# PCB_3U_SMA.net
KiCad netlist of a schematic drawn in Altium Designer
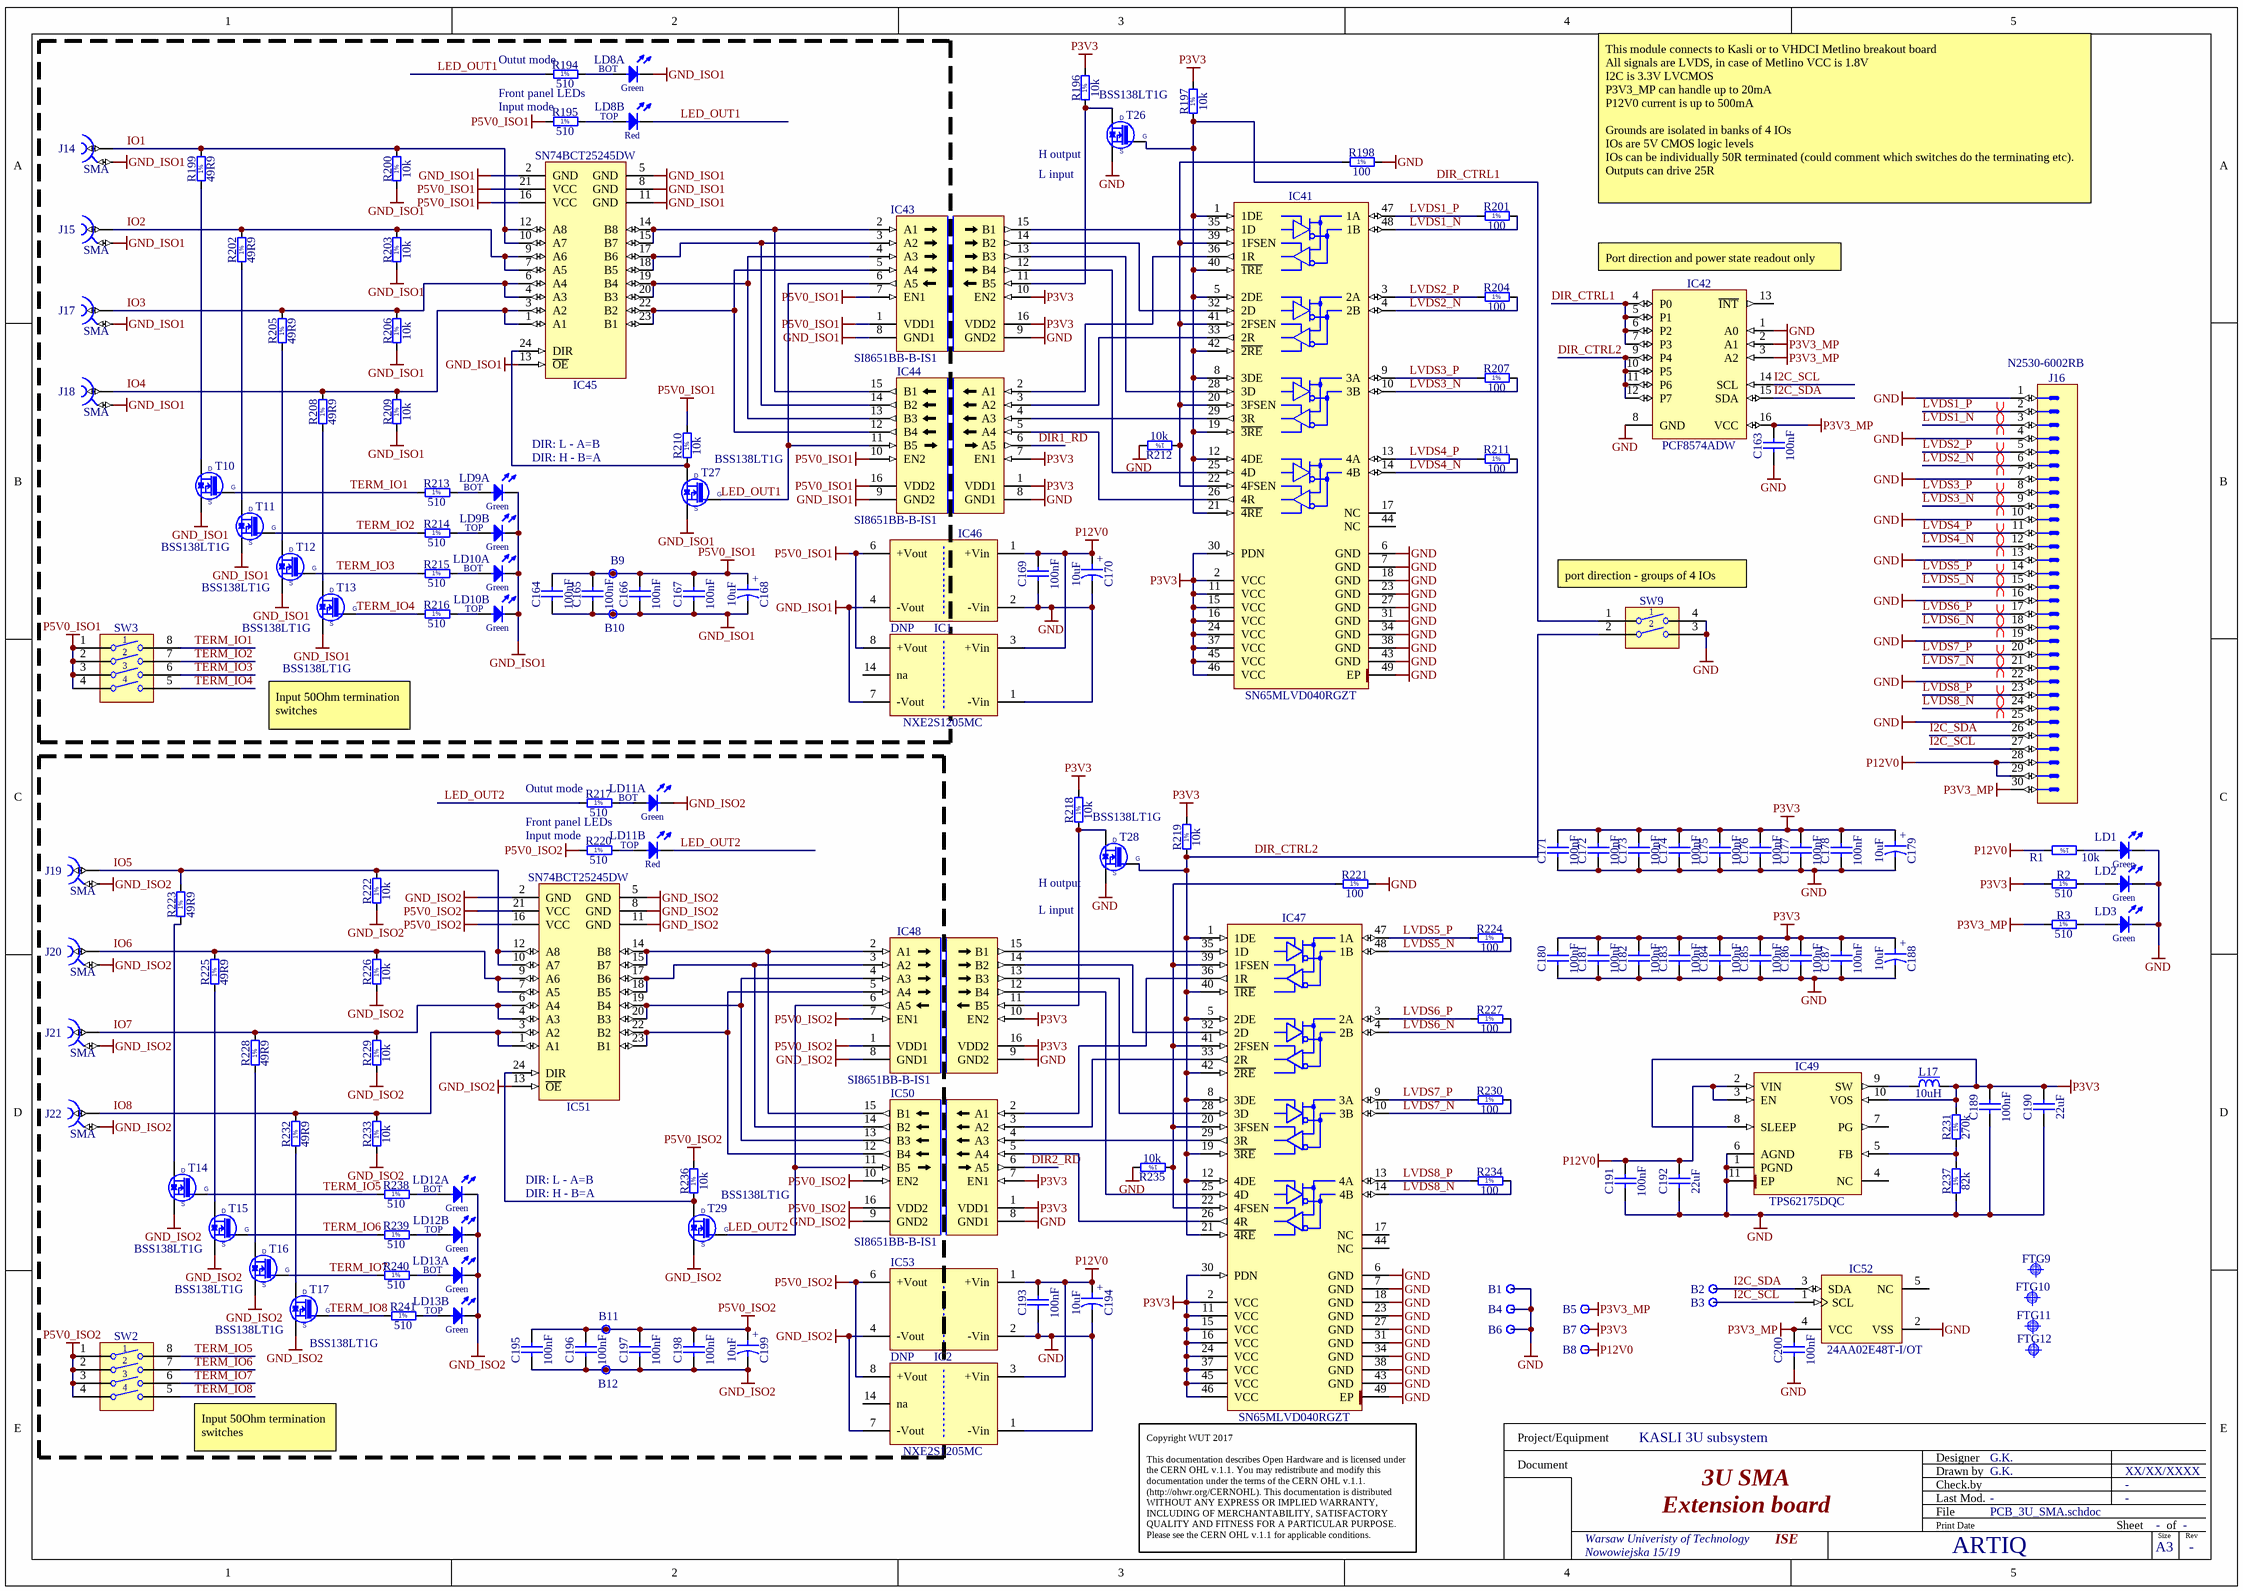
[diagram p0: PCB_3U_SMA.schdoc]

(export (version "E")
  (design (tool "Eeschema 10.0.6"))
  (components
    (comp (ref "B1")
      (value "Plated Hole")
      (footprint "c130h60")
      (description "Single Terminal Socket")
      (fields (field (name "PART NUMBER") "PLATED_HOLE0.6_PAD1.3") (field (name "AUTHOR") "CERN DEM MR"))
      (libsource (lib "Eletro-mechanical") (part "Single Terminal Socket"))
    )
    (comp (ref "B2")
      (value "Plated Hole")
      (footprint "c130h60")
      (description "Single Terminal Socket")
      (fields (field (name "PART NUMBER") "PLATED_HOLE0.6_PAD1.3") (field (name "AUTHOR") "CERN DEM MR"))
      (libsource (lib "Eletro-mechanical") (part "Single Terminal Socket"))
    )
    (comp (ref "B3")
      (value "Plated Hole")
      (footprint "c130h60")
      (description "Single Terminal Socket")
      (fields (field (name "PART NUMBER") "PLATED_HOLE0.6_PAD1.3") (field (name "AUTHOR") "CERN DEM MR"))
      (libsource (lib "Eletro-mechanical") (part "Single Terminal Socket"))
    )
    (comp (ref "B4")
      (value "Plated Hole")
      (footprint "c130h60")
      (description "Single Terminal Socket")
      (fields (field (name "PART NUMBER") "PLATED_HOLE0.6_PAD1.3") (field (name "AUTHOR") "CERN DEM MR"))
      (libsource (lib "Eletro-mechanical") (part "Single Terminal Socket"))
    )
    (comp (ref "B5")
      (value "Plated Hole")
      (footprint "c130h60")
      (description "Single Terminal Socket")
      (fields (field (name "PART NUMBER") "PLATED_HOLE0.6_PAD1.3") (field (name "AUTHOR") "CERN DEM MR"))
      (libsource (lib "Eletro-mechanical") (part "Single Terminal Socket"))
    )
    (comp (ref "B6")
      (value "Plated Hole")
      (footprint "c130h60")
      (description "Single Terminal Socket")
      (fields (field (name "PART NUMBER") "PLATED_HOLE0.6_PAD1.3") (field (name "AUTHOR") "CERN DEM MR"))
      (libsource (lib "Eletro-mechanical") (part "Single Terminal Socket"))
    )
    (comp (ref "B7")
      (value "Plated Hole")
      (footprint "c130h60")
      (description "Single Terminal Socket")
      (fields (field (name "PART NUMBER") "PLATED_HOLE0.6_PAD1.3") (field (name "AUTHOR") "CERN DEM MR"))
      (libsource (lib "Eletro-mechanical") (part "Single Terminal Socket"))
    )
    (comp (ref "B8")
      (value "Plated Hole")
      (footprint "c130h60")
      (description "Single Terminal Socket")
      (fields (field (name "PART NUMBER") "PLATED_HOLE0.6_PAD1.3") (field (name "AUTHOR") "CERN DEM MR"))
      (libsource (lib "Eletro-mechanical") (part "Single Terminal Socket"))
    )
    (comp (ref "B9")
      (value "Plated Hole")
      (footprint "c130h60")
      (description "Single Terminal Socket")
      (fields (field (name "PART NUMBER") "PLATED_HOLE0.6_PAD1.3") (field (name "AUTHOR") "CERN DEM MR"))
      (libsource (lib "Eletro-mechanical") (part "Single Terminal Socket"))
    )
    (comp (ref "B10")
      (value "Plated Hole")
      (footprint "c130h60")
      (description "Single Terminal Socket")
      (fields (field (name "PART NUMBER") "PLATED_HOLE0.6_PAD1.3") (field (name "AUTHOR") "CERN DEM MR"))
      (libsource (lib "Eletro-mechanical") (part "Single Terminal Socket"))
    )
    (comp (ref "B11")
      (value "Plated Hole")
      (footprint "c130h60")
      (description "Single Terminal Socket")
      (fields (field (name "PART NUMBER") "PLATED_HOLE0.6_PAD1.3") (field (name "AUTHOR") "CERN DEM MR"))
      (libsource (lib "Eletro-mechanical") (part "Single Terminal Socket"))
    )
    (comp (ref "B12")
      (value "Plated Hole")
      (footprint "c130h60")
      (description "Single Terminal Socket")
      (fields (field (name "PART NUMBER") "PLATED_HOLE0.6_PAD1.3") (field (name "AUTHOR") "CERN DEM MR"))
      (libsource (lib "Eletro-mechanical") (part "Single Terminal Socket"))
    )
    (comp (ref "C163")
      (value "100nF")
      (footprint "CAPC1005X55N")
      (description "Non-polarised capacitor")
      (fields
        (field (name "PART NUMBER") "CC0402_100NF_16V_10%_X5R")
        (field (name "VOLTAGE") "16V")
        (field (name "AUTHOR") "CERN DEM JLC")
      )
      (libsource (lib "Capacitors") (part "Capacitor - non polarized"))
    )
    (comp (ref "C164")
      (value "100nF")
      (footprint "CAPC1005X55N")
      (description "Non-polarised capacitor")
      (fields
        (field (name "PART NUMBER") "CC0402_100NF_16V_10%_X5R")
        (field (name "VOLTAGE") "16V")
        (field (name "AUTHOR") "CERN DEM JLC")
      )
      (libsource (lib "Capacitors") (part "Capacitor - non polarized"))
    )
    (comp (ref "C165")
      (value "100nF")
      (footprint "CAPC1005X55N")
      (description "Non-polarised capacitor")
      (fields
        (field (name "PART NUMBER") "CC0402_100NF_16V_10%_X5R")
        (field (name "VOLTAGE") "16V")
        (field (name "AUTHOR") "CERN DEM JLC")
      )
      (libsource (lib "Capacitors") (part "Capacitor - non polarized"))
    )
    (comp (ref "C166")
      (value "100nF")
      (footprint "CAPC1005X55N")
      (description "Non-polarised capacitor")
      (fields
        (field (name "PART NUMBER") "CC0402_100NF_16V_10%_X5R")
        (field (name "VOLTAGE") "16V")
        (field (name "AUTHOR") "CERN DEM JLC")
      )
      (libsource (lib "Capacitors") (part "Capacitor - non polarized"))
    )
    (comp (ref "C167")
      (value "100nF")
      (footprint "CAPC1005X55N")
      (description "Non-polarised capacitor")
      (fields
        (field (name "PART NUMBER") "CC0402_100NF_16V_10%_X5R")
        (field (name "VOLTAGE") "16V")
        (field (name "AUTHOR") "CERN DEM JLC")
      )
      (libsource (lib "Capacitors") (part "Capacitor - non polarized"))
    )
    (comp (ref "C168")
      (value "10uF")
      (footprint "CAPAE430X540N")
      (description "Polarised capacitor")
      (fields
        (field (name "PART NUMBER") "CAE430-540_10UF_16V_20%")
        (field (name "VOLTAGE") "16V")
        (field (name "AUTHOR") "CERN DEM JLC")
      )
      (libsource (lib "Capacitors") (part "Capacitor - polarized"))
    )
    (comp (ref "C169")
      (value "100nF")
      (footprint "CAPC1005X55N")
      (description "Non-polarised capacitor")
      (fields
        (field (name "PART NUMBER") "CC0402_100NF_16V_10%_X5R")
        (field (name "VOLTAGE") "16V")
        (field (name "AUTHOR") "CERN DEM JLC")
      )
      (libsource (lib "Capacitors") (part "Capacitor - non polarized"))
    )
    (comp (ref "C170")
      (value "10uF")
      (footprint "CAPAE430X540N")
      (description "Polarised capacitor")
      (fields
        (field (name "PART NUMBER") "CAE430-540_10UF_16V_20%")
        (field (name "VOLTAGE") "16V")
        (field (name "AUTHOR") "CERN DEM JLC")
      )
      (libsource (lib "Capacitors") (part "Capacitor - polarized"))
    )
    (comp (ref "C171")
      (value "100nF")
      (footprint "CAPC1005X55N")
      (description "Non-polarised capacitor")
      (fields
        (field (name "PART NUMBER") "CC0402_100NF_16V_10%_X5R")
        (field (name "VOLTAGE") "16V")
        (field (name "AUTHOR") "CERN DEM JLC")
      )
      (libsource (lib "Capacitors") (part "Capacitor - non polarized"))
    )
    (comp (ref "C172")
      (value "100nF")
      (footprint "CAPC1005X55N")
      (description "Non-polarised capacitor")
      (fields
        (field (name "PART NUMBER") "CC0402_100NF_16V_10%_X5R")
        (field (name "VOLTAGE") "16V")
        (field (name "AUTHOR") "CERN DEM JLC")
      )
      (libsource (lib "Capacitors") (part "Capacitor - non polarized"))
    )
    (comp (ref "C173")
      (value "100nF")
      (footprint "CAPC1005X55N")
      (description "Non-polarised capacitor")
      (fields
        (field (name "PART NUMBER") "CC0402_100NF_16V_10%_X5R")
        (field (name "VOLTAGE") "16V")
        (field (name "AUTHOR") "CERN DEM JLC")
      )
      (libsource (lib "Capacitors") (part "Capacitor - non polarized"))
    )
    (comp (ref "C174")
      (value "100nF")
      (footprint "CAPC1005X55N")
      (description "Non-polarised capacitor")
      (fields
        (field (name "PART NUMBER") "CC0402_100NF_16V_10%_X5R")
        (field (name "VOLTAGE") "16V")
        (field (name "AUTHOR") "CERN DEM JLC")
      )
      (libsource (lib "Capacitors") (part "Capacitor - non polarized"))
    )
    (comp (ref "C175")
      (value "100nF")
      (footprint "CAPC1005X55N")
      (description "Non-polarised capacitor")
      (fields
        (field (name "PART NUMBER") "CC0402_100NF_16V_10%_X5R")
        (field (name "VOLTAGE") "16V")
        (field (name "AUTHOR") "CERN DEM JLC")
      )
      (libsource (lib "Capacitors") (part "Capacitor - non polarized"))
    )
    (comp (ref "C176")
      (value "100nF")
      (footprint "CAPC1005X55N")
      (description "Non-polarised capacitor")
      (fields
        (field (name "PART NUMBER") "CC0402_100NF_16V_10%_X5R")
        (field (name "VOLTAGE") "16V")
        (field (name "AUTHOR") "CERN DEM JLC")
      )
      (libsource (lib "Capacitors") (part "Capacitor - non polarized"))
    )
    (comp (ref "C177")
      (value "100nF")
      (footprint "CAPC1005X55N")
      (description "Non-polarised capacitor")
      (fields
        (field (name "PART NUMBER") "CC0402_100NF_16V_10%_X5R")
        (field (name "VOLTAGE") "16V")
        (field (name "AUTHOR") "CERN DEM JLC")
      )
      (libsource (lib "Capacitors") (part "Capacitor - non polarized"))
    )
    (comp (ref "C178")
      (value "100nF")
      (footprint "CAPC1005X55N")
      (description "Non-polarised capacitor")
      (fields
        (field (name "PART NUMBER") "CC0402_100NF_16V_10%_X5R")
        (field (name "VOLTAGE") "16V")
        (field (name "AUTHOR") "CERN DEM JLC")
      )
      (libsource (lib "Capacitors") (part "Capacitor - non polarized"))
    )
    (comp (ref "C179")
      (value "10uF")
      (footprint "CAPAE430X540N")
      (description "Polarised capacitor")
      (fields
        (field (name "PART NUMBER") "CAE430-540_10UF_16V_20%")
        (field (name "VOLTAGE") "16V")
        (field (name "AUTHOR") "CERN DEM JLC")
      )
      (libsource (lib "Capacitors") (part "Capacitor - polarized"))
    )
    (comp (ref "C180")
      (value "100nF")
      (footprint "CAPC1005X55N")
      (description "Non-polarised capacitor")
      (fields
        (field (name "PART NUMBER") "CC0402_100NF_16V_10%_X5R")
        (field (name "VOLTAGE") "16V")
        (field (name "AUTHOR") "CERN DEM JLC")
      )
      (libsource (lib "Capacitors") (part "Capacitor - non polarized"))
    )
    (comp (ref "C181")
      (value "100nF")
      (footprint "CAPC1005X55N")
      (description "Non-polarised capacitor")
      (fields
        (field (name "PART NUMBER") "CC0402_100NF_16V_10%_X5R")
        (field (name "VOLTAGE") "16V")
        (field (name "AUTHOR") "CERN DEM JLC")
      )
      (libsource (lib "Capacitors") (part "Capacitor - non polarized"))
    )
    (comp (ref "C182")
      (value "100nF")
      (footprint "CAPC1005X55N")
      (description "Non-polarised capacitor")
      (fields
        (field (name "PART NUMBER") "CC0402_100NF_16V_10%_X5R")
        (field (name "VOLTAGE") "16V")
        (field (name "AUTHOR") "CERN DEM JLC")
      )
      (libsource (lib "Capacitors") (part "Capacitor - non polarized"))
    )
    (comp (ref "C183")
      (value "100nF")
      (footprint "CAPC1005X55N")
      (description "Non-polarised capacitor")
      (fields
        (field (name "PART NUMBER") "CC0402_100NF_16V_10%_X5R")
        (field (name "VOLTAGE") "16V")
        (field (name "AUTHOR") "CERN DEM JLC")
      )
      (libsource (lib "Capacitors") (part "Capacitor - non polarized"))
    )
    (comp (ref "C184")
      (value "100nF")
      (footprint "CAPC1005X55N")
      (description "Non-polarised capacitor")
      (fields
        (field (name "PART NUMBER") "CC0402_100NF_16V_10%_X5R")
        (field (name "VOLTAGE") "16V")
        (field (name "AUTHOR") "CERN DEM JLC")
      )
      (libsource (lib "Capacitors") (part "Capacitor - non polarized"))
    )
    (comp (ref "C185")
      (value "100nF")
      (footprint "CAPC1005X55N")
      (description "Non-polarised capacitor")
      (fields
        (field (name "PART NUMBER") "CC0402_100NF_16V_10%_X5R")
        (field (name "VOLTAGE") "16V")
        (field (name "AUTHOR") "CERN DEM JLC")
      )
      (libsource (lib "Capacitors") (part "Capacitor - non polarized"))
    )
    (comp (ref "C186")
      (value "100nF")
      (footprint "CAPC1005X55N")
      (description "Non-polarised capacitor")
      (fields
        (field (name "PART NUMBER") "CC0402_100NF_16V_10%_X5R")
        (field (name "VOLTAGE") "16V")
        (field (name "AUTHOR") "CERN DEM JLC")
      )
      (libsource (lib "Capacitors") (part "Capacitor - non polarized"))
    )
    (comp (ref "C187")
      (value "100nF")
      (footprint "CAPC1005X55N")
      (description "Non-polarised capacitor")
      (fields
        (field (name "PART NUMBER") "CC0402_100NF_16V_10%_X5R")
        (field (name "VOLTAGE") "16V")
        (field (name "AUTHOR") "CERN DEM JLC")
      )
      (libsource (lib "Capacitors") (part "Capacitor - non polarized"))
    )
    (comp (ref "C188")
      (value "10uF")
      (footprint "CAPAE430X540N")
      (description "Polarised capacitor")
      (fields
        (field (name "PART NUMBER") "CAE430-540_10UF_16V_20%")
        (field (name "VOLTAGE") "16V")
        (field (name "AUTHOR") "CERN DEM JLC")
      )
      (libsource (lib "Capacitors") (part "Capacitor - polarized"))
    )
    (comp (ref "C189")
      (value "100nF")
      (footprint "CAPC1005X55N")
      (description "Non-polarised capacitor")
      (fields
        (field (name "PART NUMBER") "CC0402_100NF_16V_10%_X5R")
        (field (name "VOLTAGE") "16V")
        (field (name "AUTHOR") "CERN DEM JLC")
      )
      (libsource (lib "Capacitors") (part "Capacitor - non polarized"))
    )
    (comp (ref "C190")
      (value "22uF")
      (footprint "CAPC2012X135N")
      (description "Non-polarised capacitor")
      (fields
        (field (name "PART NUMBER") "CC0805_22UF_16V_10%_X5R")
        (field (name "VOLTAGE") "16V")
        (field (name "AUTHOR") "CERN DEM JLC")
      )
      (libsource (lib "Capacitors") (part "Capacitor - non polarized"))
    )
    (comp (ref "C191")
      (value "100nF")
      (footprint "CAPC1005X55N")
      (description "Non-polarised capacitor")
      (fields
        (field (name "PART NUMBER") "CC0402_100NF_16V_10%_X5R")
        (field (name "VOLTAGE") "16V")
        (field (name "AUTHOR") "CERN DEM JLC")
      )
      (libsource (lib "Capacitors") (part "Capacitor - non polarized"))
    )
    (comp (ref "C192")
      (value "22uF")
      (footprint "CAPC2012X135N")
      (description "Non-polarised capacitor")
      (fields
        (field (name "PART NUMBER") "CC0805_22UF_16V_10%_X5R")
        (field (name "VOLTAGE") "16V")
        (field (name "AUTHOR") "CERN DEM JLC")
      )
      (libsource (lib "Capacitors") (part "Capacitor - non polarized"))
    )
    (comp (ref "C193")
      (value "100nF")
      (footprint "CAPC1005X55N")
      (description "Non-polarised capacitor")
      (fields
        (field (name "PART NUMBER") "CC0402_100NF_16V_10%_X5R")
        (field (name "VOLTAGE") "16V")
        (field (name "AUTHOR") "CERN DEM JLC")
      )
      (libsource (lib "Capacitors") (part "Capacitor - non polarized"))
    )
    (comp (ref "C194")
      (value "10uF")
      (footprint "CAPAE430X540N")
      (description "Polarised capacitor")
      (fields
        (field (name "PART NUMBER") "CAE430-540_10UF_16V_20%")
        (field (name "VOLTAGE") "16V")
        (field (name "AUTHOR") "CERN DEM JLC")
      )
      (libsource (lib "Capacitors") (part "Capacitor - polarized"))
    )
    (comp (ref "C195")
      (value "100nF")
      (footprint "CAPC1005X55N")
      (description "Non-polarised capacitor")
      (fields
        (field (name "PART NUMBER") "CC0402_100NF_16V_10%_X5R")
        (field (name "VOLTAGE") "16V")
        (field (name "AUTHOR") "CERN DEM JLC")
      )
      (libsource (lib "Capacitors") (part "Capacitor - non polarized"))
    )
    (comp (ref "C196")
      (value "100nF")
      (footprint "CAPC1005X55N")
      (description "Non-polarised capacitor")
      (fields
        (field (name "PART NUMBER") "CC0402_100NF_16V_10%_X5R")
        (field (name "VOLTAGE") "16V")
        (field (name "AUTHOR") "CERN DEM JLC")
      )
      (libsource (lib "Capacitors") (part "Capacitor - non polarized"))
    )
    (comp (ref "C197")
      (value "100nF")
      (footprint "CAPC1005X55N")
      (description "Non-polarised capacitor")
      (fields
        (field (name "PART NUMBER") "CC0402_100NF_16V_10%_X5R")
        (field (name "VOLTAGE") "16V")
        (field (name "AUTHOR") "CERN DEM JLC")
      )
      (libsource (lib "Capacitors") (part "Capacitor - non polarized"))
    )
    (comp (ref "C198")
      (value "100nF")
      (footprint "CAPC1005X55N")
      (description "Non-polarised capacitor")
      (fields
        (field (name "PART NUMBER") "CC0402_100NF_16V_10%_X5R")
        (field (name "VOLTAGE") "16V")
        (field (name "AUTHOR") "CERN DEM JLC")
      )
      (libsource (lib "Capacitors") (part "Capacitor - non polarized"))
    )
    (comp (ref "C199")
      (value "10uF")
      (footprint "CAPAE430X540N")
      (description "Polarised capacitor")
      (fields
        (field (name "PART NUMBER") "CAE430-540_10UF_16V_20%")
        (field (name "VOLTAGE") "16V")
        (field (name "AUTHOR") "CERN DEM JLC")
      )
      (libsource (lib "Capacitors") (part "Capacitor - polarized"))
    )
    (comp (ref "C200")
      (value "100nF")
      (footprint "CAPC1005X55N")
      (description "Non-polarised capacitor")
      (fields
        (field (name "PART NUMBER") "CC0402_100NF_16V_10%_X5R")
        (field (name "VOLTAGE") "16V")
        (field (name "AUTHOR") "CERN DEM JLC")
      )
      (libsource (lib "Capacitors") (part "Capacitor - non polarized"))
    )
    (comp (ref "FTG9")
      (value "Use only in PCB")
      (footprint "FIDUCIAL_TOP_C100-200")
      (description "Fiducial Target")
      (fields (field (name "PART NUMBER") "FIDUCIAL_TARGET_C100-200") (field (name "AUTHOR") "CERN DEM JLC"))
      (libsource (lib "Eletro-mechanical") (part "Fiducial Target"))
    )
    (comp (ref "FTG10")
      (value "Use only in PCB")
      (footprint "FIDUCIAL_TOP_S100-200")
      (description "Fiducial Target")
      (fields (field (name "PART NUMBER") "FIDUCIAL_TARGET_S100-200") (field (name "AUTHOR") "CERN DEM JLC"))
      (libsource (lib "Eletro-mechanical") (part "Fiducial Target"))
    )
    (comp (ref "FTG11")
      (value "Use only in PCB")
      (footprint "FIDUCIAL_TOP_S200-400")
      (description "Fiducial Target")
      (fields (field (name "PART NUMBER") "FIDUCIAL_TARGET_S200-400") (field (name "AUTHOR") "CERN DEM JLC"))
      (libsource (lib "Eletro-mechanical") (part "Fiducial Target"))
    )
    (comp (ref "FTG12")
      (value "Use only in PCB")
      (footprint "FIDUCIAL_TOP_S100-200")
      (description "Fiducial Target")
      (fields (field (name "PART NUMBER") "FIDUCIAL_TARGET_S100-200") (field (name "AUTHOR") "CERN DEM JLC"))
      (libsource (lib "Eletro-mechanical") (part "Fiducial Target"))
    )
    (comp (ref "IC1")
      (value "NXE2S1205MC")
      (footprint "DCDC_MURATA_NXE2")
      (description "MURATA, NXE2 Serie, Dual Output DCDC Converter")
      (fields (field (name "MANUFACTURER") "MURATA POWER SOLUTIONS") (field (name "AUTHOR") "CERN DEM MR"))
      (libsource (lib "LIBRARY_SCH") (part "DCDC_MURATA_NXE2S1205MC"))
    )
    (comp (ref "IC2")
      (value "NXE2S1205MC")
      (footprint "DCDC_MURATA_NXE2")
      (description "MURATA, NXE2 Serie, Dual Output DCDC Converter")
      (fields (field (name "MANUFACTURER") "MURATA POWER SOLUTIONS") (field (name "AUTHOR") "CERN DEM MR"))
      (libsource (lib "LIBRARY_SCH") (part "DCDC_MURATA_NXE2S1205MC"))
    )
    (comp (ref "IC41")
      (value "SN65MLVD040RGZT")
      (footprint "QFN50P700X700X100-49N-S420")
      (description "4-Channel Half-Duplex M-LVDS Line Transceiver")
      (fields (field (name "MANUFACTURER") "TEXAS INSTRUMENTS") (field (name "AUTHOR") "CERN DEM JLC"))
      (libsource (lib "ICs And Semiconductors") (part "SN65MLVD040"))
    )
    (comp (ref "IC42")
      (value "PCF8574ADW")
      (footprint "SOIC127P1030X265-16N")
      (description "Remote 8-bit I/O Expander For I2C Bus")
      (fields (field (name "MANUFACTURER") "TEXAS INSTRUMENTS") (field (name "AUTHOR") "CERN DEM JLC"))
      (libsource (lib "ICs And Semiconductors") (part "PCF8574ADW"))
    )
    (comp (ref "IC43")
      (value "SI8651BB-B-IS1")
      (footprint "SOIC127P600X175-16N")
      (description "Low Power Five-Channel Digital Isolator")
      (fields (field (name "MANUFACTURER") "SILICON LABS") (field (name "AUTHOR") "CERN DEM JLC"))
      (libsource (lib "ICs And Semiconductors") (part "Si8651"))
    )
    (comp (ref "IC44")
      (value "SI8651BB-B-IS1")
      (footprint "SOIC127P600X175-16N")
      (description "Low Power Five-Channel Digital Isolator")
      (fields (field (name "MANUFACTURER") "SILICON LABS") (field (name "AUTHOR") "CERN DEM JLC"))
      (libsource (lib "") (part "Si8651_1"))
    )
    (comp (ref "IC45")
      (value "SN74BCT25245DW")
      (footprint "SOIC127P1030X265-24N")
      (description "25 Ohms Octal Bus Transceiver With 3-State Outputs")
      (fields (field (name "MANUFACTURER") "TEXAS INSTRUMENTS") (field (name "AUTHOR") "CERN DEM JLC"))
      (libsource (lib "ICs And Semiconductors") (part "7425245"))
    )
    (comp (ref "IC46")
      (value "DNP")
      (footprint "DCDC_TRACO_TMA")
      (description "1 W Watt, 10.8-13.2VDCVin, 5 V@0.2 A")
      (fields
        (field (name "PART NUMBER") "TMA 1205S")
        (field (name "MANUFACTURER") "TRACO POWER")
        (field (name "AUTHOR") "GK")
      )
      (libsource (lib "LIBRARY_SCH") (part "DC/DC_TRACO_TMA1205S"))
    )
    (comp (ref "IC47")
      (value "SN65MLVD040RGZT")
      (footprint "QFN50P700X700X100-49N-S420")
      (description "4-Channel Half-Duplex M-LVDS Line Transceiver")
      (fields (field (name "MANUFACTURER") "TEXAS INSTRUMENTS") (field (name "AUTHOR") "CERN DEM JLC"))
      (libsource (lib "ICs And Semiconductors") (part "SN65MLVD040"))
    )
    (comp (ref "IC48")
      (value "SI8651BB-B-IS1")
      (footprint "SOIC127P600X175-16N")
      (description "Low Power Five-Channel Digital Isolator")
      (fields (field (name "MANUFACTURER") "SILICON LABS") (field (name "AUTHOR") "CERN DEM JLC"))
      (libsource (lib "ICs And Semiconductors") (part "Si8651"))
    )
    (comp (ref "IC49")
      (value "TPS62175DQC")
      (footprint "SON50P200X300X80-11N-R94X250")
      (description "4.75-28VDC to 1-6VDC, 500mA Step-Down Converter With Sleep Mode")
      (fields (field (name "MANUFACTURER") "TEXAS INSTRUMENTS") (field (name "AUTHOR") "CERN DEM JMW"))
      (libsource (lib "ICs And Semiconductors") (part "TPS62175"))
    )
    (comp (ref "IC50")
      (value "SI8651BB-B-IS1")
      (footprint "SOIC127P600X175-16N")
      (description "Low Power Five-Channel Digital Isolator")
      (fields (field (name "MANUFACTURER") "SILICON LABS") (field (name "AUTHOR") "CERN DEM JLC"))
      (libsource (lib "") (part "Si8651_1"))
    )
    (comp (ref "IC51")
      (value "SN74BCT25245DW")
      (footprint "SOIC127P1030X265-24N")
      (description "25 Ohms Octal Bus Transceiver With 3-State Outputs")
      (fields (field (name "MANUFACTURER") "TEXAS INSTRUMENTS") (field (name "AUTHOR") "CERN DEM JLC"))
      (libsource (lib "ICs And Semiconductors") (part "7425245"))
    )
    (comp (ref "IC52")
      (value "24AA02E48T-I/OT")
      (footprint "SOT95P280X145-5N")
      (description "1.7V-5.5V, 2K I2C Serial EEPROM With EUI-48 Node Identity")
      (fields (field (name "MANUFACTURER") "MICROCHIP TECHNOLOGY") (field (name "AUTHOR") "CERN DEM MR"))
      (libsource (lib "ICs And Semiconductors") (part "24AA02E48T-I/OT"))
    )
    (comp (ref "IC53")
      (value "DNP")
      (footprint "DCDC_TRACO_TMA")
      (description "1 W Watt, 10.8-13.2VDCVin, 5 V@0.2 A")
      (fields
        (field (name "PART NUMBER") "TMA 1205S")
        (field (name "MANUFACTURER") "TRACO POWER")
        (field (name "AUTHOR") "GK")
      )
      (libsource (lib "LIBRARY_SCH") (part "DC/DC_TRACO_TMA1205S"))
    )
    (comp (ref "J14")
      (value "SMA")
      (footprint "MOLEX_73251-2120")
      (description "50 Ohm, SMA Edge Mount PCB, With Jam Nut And Lock Washer")
      (fields
        (field (name "PART NUMBER") "MOLEX_73251-2120")
        (field (name "MANUFACTURER") "MOLEX")
        (field (name "AUTHOR") "CERN DEM JLC")
      )
      (libsource (lib "LIBRARY_SCH") (part "CON_SMA_RA_SMD_73251-2120"))
    )
    (comp (ref "J15")
      (value "SMA")
      (footprint "SMA209F")
      (description "50 Ohm Through Hole SMA Right Angle PCB Jack")
      (fields
        (field (name "PART NUMBER") "SMA209F")
        (field (name "MANUFACTURER") "S-Conn")
        (field (name "AUTHOR") "GK")
      )
      (libsource (lib "LIBRARY_SCH") (part "CON_SMA_SMA209F"))
    )
    (comp (ref "J16")
      (value "~")
      (footprint "3M_N2530-6002RB")
      (description "Connector 30 Male")
      (fields
        (field (name "PART NUMBER") "3M_N2530-6002RB")
        (field (name "MANUFACTURER") "3M")
        (field (name "MANUFACTURER PART NUMBER") "N2530-6002RB")
        (field (name "AUTHOR") "CERN DEM JLC")
      )
      (libsource (lib "Connectors") (part "Connector 30 Male"))
    )
    (comp (ref "J17")
      (value "SMA")
      (footprint "MOLEX_73251-2120")
      (description "50 Ohm, SMA Edge Mount PCB, With Jam Nut And Lock Washer")
      (fields
        (field (name "PART NUMBER") "MOLEX_73251-2120")
        (field (name "MANUFACTURER") "MOLEX")
        (field (name "AUTHOR") "CERN DEM JLC")
      )
      (libsource (lib "LIBRARY_SCH") (part "CON_SMA_RA_SMD_73251-2120"))
    )
    (comp (ref "J18")
      (value "SMA")
      (footprint "SMA209F")
      (description "50 Ohm Through Hole SMA Right Angle PCB Jack")
      (fields
        (field (name "PART NUMBER") "SMA209F")
        (field (name "MANUFACTURER") "S-Conn")
        (field (name "AUTHOR") "GK")
      )
      (libsource (lib "LIBRARY_SCH") (part "CON_SMA_SMA209F"))
    )
    (comp (ref "J19")
      (value "SMA")
      (footprint "MOLEX_73251-2120")
      (description "50 Ohm, SMA Edge Mount PCB, With Jam Nut And Lock Washer")
      (fields
        (field (name "PART NUMBER") "MOLEX_73251-2120")
        (field (name "MANUFACTURER") "MOLEX")
        (field (name "AUTHOR") "CERN DEM JLC")
      )
      (libsource (lib "LIBRARY_SCH") (part "CON_SMA_RA_SMD_73251-2120"))
    )
    (comp (ref "J20")
      (value "SMA")
      (footprint "SMA209F")
      (description "50 Ohm Through Hole SMA Right Angle PCB Jack")
      (fields
        (field (name "PART NUMBER") "SMA209F")
        (field (name "MANUFACTURER") "S-Conn")
        (field (name "AUTHOR") "GK")
      )
      (libsource (lib "LIBRARY_SCH") (part "CON_SMA_SMA209F"))
    )
    (comp (ref "J21")
      (value "SMA")
      (footprint "MOLEX_73251-2120")
      (description "50 Ohm, SMA Edge Mount PCB, With Jam Nut And Lock Washer")
      (fields
        (field (name "PART NUMBER") "MOLEX_73251-2120")
        (field (name "MANUFACTURER") "MOLEX")
        (field (name "AUTHOR") "CERN DEM JLC")
      )
      (libsource (lib "LIBRARY_SCH") (part "CON_SMA_RA_SMD_73251-2120"))
    )
    (comp (ref "J22")
      (value "SMA")
      (footprint "SMA209F")
      (description "50 Ohm Through Hole SMA Right Angle PCB Jack")
      (fields
        (field (name "PART NUMBER") "SMA209F")
        (field (name "MANUFACTURER") "S-Conn")
        (field (name "AUTHOR") "GK")
      )
      (libsource (lib "LIBRARY_SCH") (part "CON_SMA_SMA209F"))
    )
    (comp (ref "L17")
      (value "10uH")
      (footprint "IND_MURATA-PS_8400")
      (description "Inductor With Core")
      (fields
        (field (name "PART NUMBER") "IND_10UH_10%_MURATA-PS_8400")
        (field (name "POWER") "950mA")
        (field (name "AUTHOR") "CERN DEM JLC")
      )
      (libsource (lib "Inductors & Transformers") (part "Inductor With Magnetic core"))
    )
    (comp (ref "LD1")
      (value "Green")
      (footprint "LED_KINGBRIGHT_KPH-1608CGCK")
      (description "LED Green 1C 2A")
      (fields
        (field (name "PART NUMBER") "LED_KINGBRIGHT_KPH-1608CGCK")
        (field (name "MANUFACTURER") "KINGBRIGHT")
        (field (name "AUTHOR") "CERN DEM JLC")
      )
      (libsource (lib "ICs And Semiconductors") (part "LED Green 1C 2A"))
    )
    (comp (ref "LD2")
      (value "Green")
      (footprint "LED_KINGBRIGHT_KPH-1608CGCK")
      (description "LED Green 1C 2A")
      (fields
        (field (name "PART NUMBER") "LED_KINGBRIGHT_KPH-1608CGCK")
        (field (name "MANUFACTURER") "KINGBRIGHT")
        (field (name "AUTHOR") "CERN DEM JLC")
      )
      (libsource (lib "ICs And Semiconductors") (part "LED Green 1C 2A"))
    )
    (comp (ref "LD3")
      (value "Green")
      (footprint "LED_KINGBRIGHT_KPH-1608CGCK")
      (description "LED Green 1C 2A")
      (fields
        (field (name "PART NUMBER") "LED_KINGBRIGHT_KPH-1608CGCK")
        (field (name "MANUFACTURER") "KINGBRIGHT")
        (field (name "AUTHOR") "CERN DEM JLC")
      )
      (libsource (lib "ICs And Semiconductors") (part "LED Green 1C 2A"))
    )
    (comp (ref "LD8")
      (value "Red/Green")
      (footprint "LED_DIALIGHT_571-0112F")
      (description "2x LED  Botom Green, Top Red")
      (fields
        (field (name "PART NUMBER") "LED_DIALIGHT_571-0112F")
        (field (name "MANUFACTURER") "DIALIGHT")
        (field (name "AUTHOR") "CERN DEM JLC")
      )
      (libsource (lib "ICs And Semiconductors") (part "LED x2 G-1C2A-BOT_R-3C4A-TOP"))
    )
    (comp (ref "LD9")
      (value "Green/Green")
      (footprint "LED_DIALIGHT_571-0122F")
      (description "LED x2 Green 1C2A-BOT_3C4A-TOP")
      (fields
        (field (name "PART NUMBER") "LED_DIALIGHT_571-0122F")
        (field (name "MANUFACTURER") "DIALIGHT")
        (field (name "AUTHOR") "CERN DEM JLC")
      )
      (libsource (lib "ICs And Semiconductors") (part "LED x2 Green 1C2A-BOT_3C4A-TOP"))
    )
    (comp (ref "LD10")
      (value "Green/Green")
      (footprint "LED_DIALIGHT_571-0122F")
      (description "LED x2 Green 1C2A-BOT_3C4A-TOP")
      (fields
        (field (name "PART NUMBER") "LED_DIALIGHT_571-0122F")
        (field (name "MANUFACTURER") "DIALIGHT")
        (field (name "AUTHOR") "CERN DEM JLC")
      )
      (libsource (lib "ICs And Semiconductors") (part "LED x2 Green 1C2A-BOT_3C4A-TOP"))
    )
    (comp (ref "LD11")
      (value "Red/Green")
      (footprint "LED_DIALIGHT_571-0112F")
      (description "2x LED  Botom Green, Top Red")
      (fields
        (field (name "PART NUMBER") "LED_DIALIGHT_571-0112F")
        (field (name "MANUFACTURER") "DIALIGHT")
        (field (name "AUTHOR") "CERN DEM JLC")
      )
      (libsource (lib "ICs And Semiconductors") (part "LED x2 G-1C2A-BOT_R-3C4A-TOP"))
    )
    (comp (ref "LD12")
      (value "Green/Green")
      (footprint "LED_DIALIGHT_571-0122F")
      (description "LED x2 Green 1C2A-BOT_3C4A-TOP")
      (fields
        (field (name "PART NUMBER") "LED_DIALIGHT_571-0122F")
        (field (name "MANUFACTURER") "DIALIGHT")
        (field (name "AUTHOR") "CERN DEM JLC")
      )
      (libsource (lib "ICs And Semiconductors") (part "LED x2 Green 1C2A-BOT_3C4A-TOP"))
    )
    (comp (ref "LD13")
      (value "Green/Green")
      (footprint "LED_DIALIGHT_571-0122F")
      (description "LED x2 Green 1C2A-BOT_3C4A-TOP")
      (fields
        (field (name "PART NUMBER") "LED_DIALIGHT_571-0122F")
        (field (name "MANUFACTURER") "DIALIGHT")
        (field (name "AUTHOR") "CERN DEM JLC")
      )
      (libsource (lib "ICs And Semiconductors") (part "LED x2 Green 1C2A-BOT_3C4A-TOP"))
    )
    (comp (ref "R1")
      (value "10k")
      (footprint "RESC1005X40N")
      (description "Resistor - 1%")
      (fields
        (field (name "PART NUMBER") "R0402_10K_1%_0.0625W_100PPM")
        (field (name "POWER") "0.0625W")
        (field (name "AUTHOR") "CERN DEM JLC")
      )
      (libsource (lib "Resistors") (part "Resistor - 1%"))
    )
    (comp (ref "R2")
      (value "510")
      (footprint "RESC1005X40N")
      (description "Resistor - 1%")
      (fields
        (field (name "PART NUMBER") "R0402_510R_1%_0.0625W_100PPM")
        (field (name "POWER") "0.0625W")
        (field (name "AUTHOR") "CERN DEM JLC")
      )
      (libsource (lib "Resistors") (part "Resistor - 1%"))
    )
    (comp (ref "R3")
      (value "510")
      (footprint "RESC1005X40N")
      (description "Resistor - 1%")
      (fields
        (field (name "PART NUMBER") "R0402_510R_1%_0.0625W_100PPM")
        (field (name "POWER") "0.0625W")
        (field (name "AUTHOR") "CERN DEM JLC")
      )
      (libsource (lib "Resistors") (part "Resistor - 1%"))
    )
    (comp (ref "R194")
      (value "510")
      (footprint "RESC1005X40N")
      (description "Resistor - 1%")
      (fields
        (field (name "PART NUMBER") "R0402_510R_1%_0.0625W_100PPM")
        (field (name "POWER") "0.0625W")
        (field (name "AUTHOR") "CERN DEM JLC")
      )
      (libsource (lib "Resistors") (part "Resistor - 1%"))
    )
    (comp (ref "R195")
      (value "510")
      (footprint "RESC1005X40N")
      (description "Resistor - 1%")
      (fields
        (field (name "PART NUMBER") "R0402_510R_1%_0.0625W_100PPM")
        (field (name "POWER") "0.0625W")
        (field (name "AUTHOR") "CERN DEM JLC")
      )
      (libsource (lib "Resistors") (part "Resistor - 1%"))
    )
    (comp (ref "R196")
      (value "10k")
      (footprint "RESC1005X40N")
      (description "Resistor - 1%")
      (fields
        (field (name "PART NUMBER") "R0402_10K_1%_0.0625W_100PPM")
        (field (name "POWER") "0.0625W")
        (field (name "AUTHOR") "CERN DEM JLC")
      )
      (libsource (lib "Resistors") (part "Resistor - 1%"))
    )
    (comp (ref "R197")
      (value "10k")
      (footprint "RESC1005X40N")
      (description "Resistor - 1%")
      (fields
        (field (name "PART NUMBER") "R0402_10K_1%_0.0625W_100PPM")
        (field (name "POWER") "0.0625W")
        (field (name "AUTHOR") "CERN DEM JLC")
      )
      (libsource (lib "Resistors") (part "Resistor - 1%"))
    )
    (comp (ref "R198")
      (value "100")
      (footprint "RESC1005X40N")
      (description "Resistor - 1%")
      (fields
        (field (name "PART NUMBER") "R0402_100R_1%_0.1W_100PPM")
        (field (name "POWER") "0.1W")
        (field (name "AUTHOR") "CERN DEM JLC")
      )
      (libsource (lib "Resistors") (part "Resistor - 1%"))
    )
    (comp (ref "R199")
      (value "49R9")
      (footprint "RESC3225X70N")
      (description "Resistor - 1%")
      (fields
        (field (name "PART NUMBER") "R1210_49R9_1%_0.5W_100PPM_VISHAY_CRCW")
        (field (name "POWER") "0.5W")
        (field (name "AUTHOR") "CERN DEM JMW")
      )
      (libsource (lib "Resistors") (part "Resistor - 1%"))
    )
    (comp (ref "R200")
      (value "10k")
      (footprint "RESC1005X40N")
      (description "Resistor - 1%")
      (fields
        (field (name "PART NUMBER") "R0402_10K_1%_0.0625W_100PPM")
        (field (name "POWER") "0.0625W")
        (field (name "AUTHOR") "CERN DEM JLC")
      )
      (libsource (lib "Resistors") (part "Resistor - 1%"))
    )
    (comp (ref "R201")
      (value "100")
      (footprint "RESC1005X40N")
      (description "Resistor - 1%")
      (fields
        (field (name "PART NUMBER") "R0402_100R_1%_0.1W_100PPM")
        (field (name "POWER") "0.1W")
        (field (name "AUTHOR") "CERN DEM JLC")
      )
      (libsource (lib "Resistors") (part "Resistor - 1%"))
    )
    (comp (ref "R202")
      (value "49R9")
      (footprint "RESC3225X70N")
      (description "Resistor - 1%")
      (fields
        (field (name "PART NUMBER") "R1210_49R9_1%_0.5W_100PPM_VISHAY_CRCW")
        (field (name "POWER") "0.5W")
        (field (name "AUTHOR") "CERN DEM JMW")
      )
      (libsource (lib "Resistors") (part "Resistor - 1%"))
    )
    (comp (ref "R203")
      (value "10k")
      (footprint "RESC1005X40N")
      (description "Resistor - 1%")
      (fields
        (field (name "PART NUMBER") "R0402_10K_1%_0.0625W_100PPM")
        (field (name "POWER") "0.0625W")
        (field (name "AUTHOR") "CERN DEM JLC")
      )
      (libsource (lib "Resistors") (part "Resistor - 1%"))
    )
    (comp (ref "R204")
      (value "100")
      (footprint "RESC1005X40N")
      (description "Resistor - 1%")
      (fields
        (field (name "PART NUMBER") "R0402_100R_1%_0.1W_100PPM")
        (field (name "POWER") "0.1W")
        (field (name "AUTHOR") "CERN DEM JLC")
      )
      (libsource (lib "Resistors") (part "Resistor - 1%"))
    )
    (comp (ref "R205")
      (value "49R9")
      (footprint "RESC3225X70N")
      (description "Resistor - 1%")
      (fields
        (field (name "PART NUMBER") "R1210_49R9_1%_0.5W_100PPM_VISHAY_CRCW")
        (field (name "POWER") "0.5W")
        (field (name "AUTHOR") "CERN DEM JMW")
      )
      (libsource (lib "Resistors") (part "Resistor - 1%"))
    )
    (comp (ref "R206")
      (value "10k")
      (footprint "RESC1005X40N")
      (description "Resistor - 1%")
      (fields
        (field (name "PART NUMBER") "R0402_10K_1%_0.0625W_100PPM")
        (field (name "POWER") "0.0625W")
        (field (name "AUTHOR") "CERN DEM JLC")
      )
      (libsource (lib "Resistors") (part "Resistor - 1%"))
    )
    (comp (ref "R207")
      (value "100")
      (footprint "RESC1005X40N")
      (description "Resistor - 1%")
      (fields
        (field (name "PART NUMBER") "R0402_100R_1%_0.1W_100PPM")
        (field (name "POWER") "0.1W")
        (field (name "AUTHOR") "CERN DEM JLC")
      )
      (libsource (lib "Resistors") (part "Resistor - 1%"))
    )
    (comp (ref "R208")
      (value "49R9")
      (footprint "RESC3225X70N")
      (description "Resistor - 1%")
      (fields
        (field (name "PART NUMBER") "R1210_49R9_1%_0.5W_100PPM_VISHAY_CRCW")
        (field (name "POWER") "0.5W")
        (field (name "AUTHOR") "CERN DEM JMW")
      )
      (libsource (lib "Resistors") (part "Resistor - 1%"))
    )
    (comp (ref "R209")
      (value "10k")
      (footprint "RESC1005X40N")
      (description "Resistor - 1%")
      (fields
        (field (name "PART NUMBER") "R0402_10K_1%_0.0625W_100PPM")
        (field (name "POWER") "0.0625W")
        (field (name "AUTHOR") "CERN DEM JLC")
      )
      (libsource (lib "Resistors") (part "Resistor - 1%"))
    )
    (comp (ref "R210")
      (value "10k")
      (footprint "RESC1005X40N")
      (description "Resistor - 1%")
      (fields
        (field (name "PART NUMBER") "R0402_10K_1%_0.0625W_100PPM")
        (field (name "POWER") "0.0625W")
        (field (name "AUTHOR") "CERN DEM JLC")
      )
      (libsource (lib "Resistors") (part "Resistor - 1%"))
    )
    (comp (ref "R211")
      (value "100")
      (footprint "RESC1005X40N")
      (description "Resistor - 1%")
      (fields
        (field (name "PART NUMBER") "R0402_100R_1%_0.1W_100PPM")
        (field (name "POWER") "0.1W")
        (field (name "AUTHOR") "CERN DEM JLC")
      )
      (libsource (lib "Resistors") (part "Resistor - 1%"))
    )
    (comp (ref "R212")
      (value "10k")
      (footprint "RESC1005X40N")
      (description "Resistor - 1%")
      (fields
        (field (name "PART NUMBER") "R0402_10K_1%_0.0625W_100PPM")
        (field (name "POWER") "0.0625W")
        (field (name "AUTHOR") "CERN DEM JLC")
      )
      (libsource (lib "Resistors") (part "Resistor - 1%"))
    )
    (comp (ref "R213")
      (value "510")
      (footprint "RESC1005X40N")
      (description "Resistor - 1%")
      (fields
        (field (name "PART NUMBER") "R0402_510R_1%_0.0625W_100PPM")
        (field (name "POWER") "0.0625W")
        (field (name "AUTHOR") "CERN DEM JLC")
      )
      (libsource (lib "Resistors") (part "Resistor - 1%"))
    )
    (comp (ref "R214")
      (value "510")
      (footprint "RESC1005X40N")
      (description "Resistor - 1%")
      (fields
        (field (name "PART NUMBER") "R0402_510R_1%_0.0625W_100PPM")
        (field (name "POWER") "0.0625W")
        (field (name "AUTHOR") "CERN DEM JLC")
      )
      (libsource (lib "Resistors") (part "Resistor - 1%"))
    )
    (comp (ref "R215")
      (value "510")
      (footprint "RESC1005X40N")
      (description "Resistor - 1%")
      (fields
        (field (name "PART NUMBER") "R0402_510R_1%_0.0625W_100PPM")
        (field (name "POWER") "0.0625W")
        (field (name "AUTHOR") "CERN DEM JLC")
      )
      (libsource (lib "Resistors") (part "Resistor - 1%"))
    )
    (comp (ref "R216")
      (value "510")
      (footprint "RESC1005X40N")
      (description "Resistor - 1%")
      (fields
        (field (name "PART NUMBER") "R0402_510R_1%_0.0625W_100PPM")
        (field (name "POWER") "0.0625W")
        (field (name "AUTHOR") "CERN DEM JLC")
      )
      (libsource (lib "Resistors") (part "Resistor - 1%"))
    )
    (comp (ref "R217")
      (value "510")
      (footprint "RESC1005X40N")
      (description "Resistor - 1%")
      (fields
        (field (name "PART NUMBER") "R0402_510R_1%_0.0625W_100PPM")
        (field (name "POWER") "0.0625W")
        (field (name "AUTHOR") "CERN DEM JLC")
      )
      (libsource (lib "Resistors") (part "Resistor - 1%"))
    )
    (comp (ref "R218")
      (value "10k")
      (footprint "RESC1005X40N")
      (description "Resistor - 1%")
      (fields
        (field (name "PART NUMBER") "R0402_10K_1%_0.0625W_100PPM")
        (field (name "POWER") "0.0625W")
        (field (name "AUTHOR") "CERN DEM JLC")
      )
      (libsource (lib "Resistors") (part "Resistor - 1%"))
    )
    (comp (ref "R219")
      (value "10k")
      (footprint "RESC1005X40N")
      (description "Resistor - 1%")
      (fields
        (field (name "PART NUMBER") "R0402_10K_1%_0.0625W_100PPM")
        (field (name "POWER") "0.0625W")
        (field (name "AUTHOR") "CERN DEM JLC")
      )
      (libsource (lib "Resistors") (part "Resistor - 1%"))
    )
    (comp (ref "R220")
      (value "510")
      (footprint "RESC1005X40N")
      (description "Resistor - 1%")
      (fields
        (field (name "PART NUMBER") "R0402_510R_1%_0.0625W_100PPM")
        (field (name "POWER") "0.0625W")
        (field (name "AUTHOR") "CERN DEM JLC")
      )
      (libsource (lib "Resistors") (part "Resistor - 1%"))
    )
    (comp (ref "R221")
      (value "100")
      (footprint "RESC1005X40N")
      (description "Resistor - 1%")
      (fields
        (field (name "PART NUMBER") "R0402_100R_1%_0.1W_100PPM")
        (field (name "POWER") "0.1W")
        (field (name "AUTHOR") "CERN DEM JLC")
      )
      (libsource (lib "Resistors") (part "Resistor - 1%"))
    )
    (comp (ref "R222")
      (value "10k")
      (footprint "RESC1005X40N")
      (description "Resistor - 1%")
      (fields
        (field (name "PART NUMBER") "R0402_10K_1%_0.0625W_100PPM")
        (field (name "POWER") "0.0625W")
        (field (name "AUTHOR") "CERN DEM JLC")
      )
      (libsource (lib "Resistors") (part "Resistor - 1%"))
    )
    (comp (ref "R223")
      (value "49R9")
      (footprint "RESC3225X70N")
      (description "Resistor - 1%")
      (fields
        (field (name "PART NUMBER") "R1210_49R9_1%_0.5W_100PPM_VISHAY_CRCW")
        (field (name "POWER") "0.5W")
        (field (name "AUTHOR") "CERN DEM JMW")
      )
      (libsource (lib "Resistors") (part "Resistor - 1%"))
    )
    (comp (ref "R224")
      (value "100")
      (footprint "RESC1005X40N")
      (description "Resistor - 1%")
      (fields
        (field (name "PART NUMBER") "R0402_100R_1%_0.1W_100PPM")
        (field (name "POWER") "0.1W")
        (field (name "AUTHOR") "CERN DEM JLC")
      )
      (libsource (lib "Resistors") (part "Resistor - 1%"))
    )
    (comp (ref "R225")
      (value "49R9")
      (footprint "RESC3225X70N")
      (description "Resistor - 1%")
      (fields
        (field (name "PART NUMBER") "R1210_49R9_1%_0.5W_100PPM_VISHAY_CRCW")
        (field (name "POWER") "0.5W")
        (field (name "AUTHOR") "CERN DEM JMW")
      )
      (libsource (lib "Resistors") (part "Resistor - 1%"))
    )
    (comp (ref "R226")
      (value "10k")
      (footprint "RESC1005X40N")
      (description "Resistor - 1%")
      (fields
        (field (name "PART NUMBER") "R0402_10K_1%_0.0625W_100PPM")
        (field (name "POWER") "0.0625W")
        (field (name "AUTHOR") "CERN DEM JLC")
      )
      (libsource (lib "Resistors") (part "Resistor - 1%"))
    )
    (comp (ref "R227")
      (value "100")
      (footprint "RESC1005X40N")
      (description "Resistor - 1%")
      (fields
        (field (name "PART NUMBER") "R0402_100R_1%_0.1W_100PPM")
        (field (name "POWER") "0.1W")
        (field (name "AUTHOR") "CERN DEM JLC")
      )
      (libsource (lib "Resistors") (part "Resistor - 1%"))
    )
    (comp (ref "R228")
      (value "49R9")
      (footprint "RESC3225X70N")
      (description "Resistor - 1%")
      (fields
        (field (name "PART NUMBER") "R1210_49R9_1%_0.5W_100PPM_VISHAY_CRCW")
        (field (name "POWER") "0.5W")
        (field (name "AUTHOR") "CERN DEM JMW")
      )
      (libsource (lib "Resistors") (part "Resistor - 1%"))
    )
    (comp (ref "R229")
      (value "10k")
      (footprint "RESC1005X40N")
      (description "Resistor - 1%")
      (fields
        (field (name "PART NUMBER") "R0402_10K_1%_0.0625W_100PPM")
        (field (name "POWER") "0.0625W")
        (field (name "AUTHOR") "CERN DEM JLC")
      )
      (libsource (lib "Resistors") (part "Resistor - 1%"))
    )
    (comp (ref "R230")
      (value "100")
      (footprint "RESC1005X40N")
      (description "Resistor - 1%")
      (fields
        (field (name "PART NUMBER") "R0402_100R_1%_0.1W_100PPM")
        (field (name "POWER") "0.1W")
        (field (name "AUTHOR") "CERN DEM JLC")
      )
      (libsource (lib "Resistors") (part "Resistor - 1%"))
    )
    (comp (ref "R231")
      (value "270k")
      (footprint "RESC1608X55N")
      (description "Resistor - 1%")
      (fields
        (field (name "PART NUMBER") "R0603_270K_1%_0.1W_100PPM")
        (field (name "POWER") "0.1W")
        (field (name "AUTHOR") "CERN DEM JLC")
      )
      (libsource (lib "Resistors") (part "Resistor - 1%"))
    )
    (comp (ref "R232")
      (value "49R9")
      (footprint "RESC3225X70N")
      (description "Resistor - 1%")
      (fields
        (field (name "PART NUMBER") "R1210_49R9_1%_0.5W_100PPM_VISHAY_CRCW")
        (field (name "POWER") "0.5W")
        (field (name "AUTHOR") "CERN DEM JMW")
      )
      (libsource (lib "Resistors") (part "Resistor - 1%"))
    )
    (comp (ref "R233")
      (value "10k")
      (footprint "RESC1005X40N")
      (description "Resistor - 1%")
      (fields
        (field (name "PART NUMBER") "R0402_10K_1%_0.0625W_100PPM")
        (field (name "POWER") "0.0625W")
        (field (name "AUTHOR") "CERN DEM JLC")
      )
      (libsource (lib "Resistors") (part "Resistor - 1%"))
    )
    (comp (ref "R234")
      (value "100")
      (footprint "RESC1005X40N")
      (description "Resistor - 1%")
      (fields
        (field (name "PART NUMBER") "R0402_100R_1%_0.1W_100PPM")
        (field (name "POWER") "0.1W")
        (field (name "AUTHOR") "CERN DEM JLC")
      )
      (libsource (lib "Resistors") (part "Resistor - 1%"))
    )
    (comp (ref "R235")
      (value "10k")
      (footprint "RESC1005X40N")
      (description "Resistor - 1%")
      (fields
        (field (name "PART NUMBER") "R0402_10K_1%_0.0625W_100PPM")
        (field (name "POWER") "0.0625W")
        (field (name "AUTHOR") "CERN DEM JLC")
      )
      (libsource (lib "Resistors") (part "Resistor - 1%"))
    )
    (comp (ref "R236")
      (value "10k")
      (footprint "RESC1005X40N")
      (description "Resistor - 1%")
      (fields
        (field (name "PART NUMBER") "R0402_10K_1%_0.0625W_100PPM")
        (field (name "POWER") "0.0625W")
        (field (name "AUTHOR") "CERN DEM JLC")
      )
      (libsource (lib "Resistors") (part "Resistor - 1%"))
    )
    (comp (ref "R237")
      (value "82k")
      (footprint "RESC1608X55N")
      (description "Resistor - 1%")
      (fields
        (field (name "PART NUMBER") "R0603_82K_1%_0.1W_100PPM")
        (field (name "POWER") "0.1W")
        (field (name "AUTHOR") "CERN DEM JLC")
      )
      (libsource (lib "Resistors") (part "Resistor - 1%"))
    )
    (comp (ref "R238")
      (value "510")
      (footprint "RESC1005X40N")
      (description "Resistor - 1%")
      (fields
        (field (name "PART NUMBER") "R0402_510R_1%_0.0625W_100PPM")
        (field (name "POWER") "0.0625W")
        (field (name "AUTHOR") "CERN DEM JLC")
      )
      (libsource (lib "Resistors") (part "Resistor - 1%"))
    )
    (comp (ref "R239")
      (value "510")
      (footprint "RESC1005X40N")
      (description "Resistor - 1%")
      (fields
        (field (name "PART NUMBER") "R0402_510R_1%_0.0625W_100PPM")
        (field (name "POWER") "0.0625W")
        (field (name "AUTHOR") "CERN DEM JLC")
      )
      (libsource (lib "Resistors") (part "Resistor - 1%"))
    )
    (comp (ref "R240")
      (value "510")
      (footprint "RESC1005X40N")
      (description "Resistor - 1%")
      (fields
        (field (name "PART NUMBER") "R0402_510R_1%_0.0625W_100PPM")
        (field (name "POWER") "0.0625W")
        (field (name "AUTHOR") "CERN DEM JLC")
      )
      (libsource (lib "Resistors") (part "Resistor - 1%"))
    )
    (comp (ref "R241")
      (value "510")
      (footprint "RESC1005X40N")
      (description "Resistor - 1%")
      (fields
        (field (name "PART NUMBER") "R0402_510R_1%_0.0625W_100PPM")
        (field (name "POWER") "0.0625W")
        (field (name "AUTHOR") "CERN DEM JLC")
      )
      (libsource (lib "Resistors") (part "Resistor - 1%"))
    )
    (comp (ref "SW2")
      (value "Switch")
      (footprint "SW_OMRON_A6S-4102-H")
      (description "4 Ways SPST DIP Switch")
      (fields
        (field (name "PART NUMBER") "SW_OMRON_A6S-4102-H")
        (field (name "MANUFACTURER") "OMRON")
        (field (name "AUTHOR") "CERN DEM JMW")
      )
      (libsource (lib "Eletro-mechanical") (part "SW 4x SPST DIP Switch"))
    )
    (comp (ref "SW3")
      (value "Switch")
      (footprint "SW_OMRON_A6S-4102-H")
      (description "4 Ways SPST DIP Switch")
      (fields
        (field (name "PART NUMBER") "SW_OMRON_A6S-4102-H")
        (field (name "MANUFACTURER") "OMRON")
        (field (name "AUTHOR") "CERN DEM JMW")
      )
      (libsource (lib "Eletro-mechanical") (part "SW 4x SPST DIP Switch"))
    )
    (comp (ref "SW9")
      (value "Switch")
      (footprint "SW_OMRON_A6S-2102-H")
      (description "2 Ways SPST DIP Switch")
      (fields
        (field (name "PART NUMBER") "SW_OMRON_A6S-2102-H")
        (field (name "MANUFACTURER") "OMRON")
        (field (name "AUTHOR") "CERN DEM JMW")
      )
      (libsource (lib "Eletro-mechanical") (part "SW 2x SPST DIP Switch"))
    )
    (comp (ref "T10")
      (value "BSS138LT1G")
      (footprint "SOT95P240X110-3N")
      (description "N-CHANNEL MOSFET WITH DIODE")
      (fields (field (name "MANUFACTURER") "ON SEMICONDUCTOR") (field (name "AUTHOR") "CERN DEM JLC"))
      (libsource (lib "ICs And Semiconductors") (part "N-MOSFET-D 1G 2S 3D"))
    )
    (comp (ref "T11")
      (value "BSS138LT1G")
      (footprint "SOT95P240X110-3N")
      (description "N-CHANNEL MOSFET WITH DIODE")
      (fields (field (name "MANUFACTURER") "ON SEMICONDUCTOR") (field (name "AUTHOR") "CERN DEM JLC"))
      (libsource (lib "ICs And Semiconductors") (part "N-MOSFET-D 1G 2S 3D"))
    )
    (comp (ref "T12")
      (value "BSS138LT1G")
      (footprint "SOT95P240X110-3N")
      (description "N-CHANNEL MOSFET WITH DIODE")
      (fields (field (name "MANUFACTURER") "ON SEMICONDUCTOR") (field (name "AUTHOR") "CERN DEM JLC"))
      (libsource (lib "ICs And Semiconductors") (part "N-MOSFET-D 1G 2S 3D"))
    )
    (comp (ref "T13")
      (value "BSS138LT1G")
      (footprint "SOT95P240X110-3N")
      (description "N-CHANNEL MOSFET WITH DIODE")
      (fields (field (name "MANUFACTURER") "ON SEMICONDUCTOR") (field (name "AUTHOR") "CERN DEM JLC"))
      (libsource (lib "ICs And Semiconductors") (part "N-MOSFET-D 1G 2S 3D"))
    )
    (comp (ref "T14")
      (value "BSS138LT1G")
      (footprint "SOT95P240X110-3N")
      (description "N-CHANNEL MOSFET WITH DIODE")
      (fields (field (name "MANUFACTURER") "ON SEMICONDUCTOR") (field (name "AUTHOR") "CERN DEM JLC"))
      (libsource (lib "ICs And Semiconductors") (part "N-MOSFET-D 1G 2S 3D"))
    )
    (comp (ref "T15")
      (value "BSS138LT1G")
      (footprint "SOT95P240X110-3N")
      (description "N-CHANNEL MOSFET WITH DIODE")
      (fields (field (name "MANUFACTURER") "ON SEMICONDUCTOR") (field (name "AUTHOR") "CERN DEM JLC"))
      (libsource (lib "ICs And Semiconductors") (part "N-MOSFET-D 1G 2S 3D"))
    )
    (comp (ref "T16")
      (value "BSS138LT1G")
      (footprint "SOT95P240X110-3N")
      (description "N-CHANNEL MOSFET WITH DIODE")
      (fields (field (name "MANUFACTURER") "ON SEMICONDUCTOR") (field (name "AUTHOR") "CERN DEM JLC"))
      (libsource (lib "ICs And Semiconductors") (part "N-MOSFET-D 1G 2S 3D"))
    )
    (comp (ref "T17")
      (value "BSS138LT1G")
      (footprint "SOT95P240X110-3N")
      (description "N-CHANNEL MOSFET WITH DIODE")
      (fields (field (name "MANUFACTURER") "ON SEMICONDUCTOR") (field (name "AUTHOR") "CERN DEM JLC"))
      (libsource (lib "ICs And Semiconductors") (part "N-MOSFET-D 1G 2S 3D"))
    )
    (comp (ref "T26")
      (value "BSS138LT1G")
      (footprint "SOT95P240X110-3N")
      (description "N-CHANNEL MOSFET WITH DIODE")
      (fields (field (name "MANUFACTURER") "ON SEMICONDUCTOR") (field (name "AUTHOR") "CERN DEM JLC"))
      (libsource (lib "ICs And Semiconductors") (part "N-MOSFET-D 1G 2S 3D"))
    )
    (comp (ref "T27")
      (value "BSS138LT1G")
      (footprint "SOT95P240X110-3N")
      (description "N-CHANNEL MOSFET WITH DIODE")
      (fields (field (name "MANUFACTURER") "ON SEMICONDUCTOR") (field (name "AUTHOR") "CERN DEM JLC"))
      (libsource (lib "ICs And Semiconductors") (part "N-MOSFET-D 1G 2S 3D"))
    )
    (comp (ref "T28")
      (value "BSS138LT1G")
      (footprint "SOT95P240X110-3N")
      (description "N-CHANNEL MOSFET WITH DIODE")
      (fields (field (name "MANUFACTURER") "ON SEMICONDUCTOR") (field (name "AUTHOR") "CERN DEM JLC"))
      (libsource (lib "ICs And Semiconductors") (part "N-MOSFET-D 1G 2S 3D"))
    )
    (comp (ref "T29")
      (value "BSS138LT1G")
      (footprint "SOT95P240X110-3N")
      (description "N-CHANNEL MOSFET WITH DIODE")
      (fields (field (name "MANUFACTURER") "ON SEMICONDUCTOR") (field (name "AUTHOR") "CERN DEM JLC"))
      (libsource (lib "ICs And Semiconductors") (part "N-MOSFET-D 1G 2S 3D"))
    )
  )
  (nets
    (net (code "1") (name "/DIR1_RD") (class "Default")
      (node (ref "IC44") (pin "6") (pinfunction "A5_6") (pintype "output"))
    )
    (net (code "2") (name "/DIR2_RD") (class "Default")
      (node (ref "IC50") (pin "6") (pinfunction "A5_6") (pintype "output"))
    )
    (net (code "3") (name "/DIR_CTRL1") (class "Default")
      (node (ref "IC41") (pin "1") (pinfunction "1DE_1") (pintype "input"))
      (node (ref "IC41") (pin "12") (pinfunction "4DE_12") (pintype "input"))
      (node (ref "IC41") (pin "19") (pinfunction "~{3RE}_19") (pintype "input"))
      (node (ref "IC41") (pin "21") (pinfunction "~{4RE}_21") (pintype "input"))
      (node (ref "IC41") (pin "40") (pinfunction "~{1RE}_40") (pintype "input"))
      (node (ref "IC41") (pin "42") (pinfunction "~{2RE}_42") (pintype "input"))
      (node (ref "IC41") (pin "5") (pinfunction "2DE_5") (pintype "input"))
      (node (ref "IC41") (pin "8") (pinfunction "3DE_8") (pintype "input"))
      (node (ref "IC42") (pin "4") (pinfunction "P0_4") (pintype "bidirectional"))
      (node (ref "IC42") (pin "5") (pinfunction "P1_5") (pintype "bidirectional"))
      (node (ref "IC42") (pin "6") (pinfunction "P2_6") (pintype "bidirectional"))
      (node (ref "IC42") (pin "7") (pinfunction "P3_7") (pintype "bidirectional"))
      (node (ref "R197") (pin "1") (pinfunction "1_1") (pintype "passive"))
      (node (ref "SW9") (pin "1") (pinfunction "1_1") (pintype "passive"))
      (node (ref "T26") (pin "1") (pinfunction "G_1") (pintype "passive"))
    )
    (net (code "4") (name "/DIR_CTRL2") (class "Default")
      (node (ref "IC42") (pin "10") (pinfunction "P5_10") (pintype "bidirectional"))
      (node (ref "IC42") (pin "11") (pinfunction "P6_11") (pintype "bidirectional"))
      (node (ref "IC42") (pin "12") (pinfunction "P7_12") (pintype "bidirectional"))
      (node (ref "IC42") (pin "9") (pinfunction "P4_9") (pintype "bidirectional"))
      (node (ref "IC47") (pin "1") (pinfunction "1DE_1") (pintype "input"))
      (node (ref "IC47") (pin "12") (pinfunction "4DE_12") (pintype "input"))
      (node (ref "IC47") (pin "19") (pinfunction "~{3RE}_19") (pintype "input"))
      (node (ref "IC47") (pin "21") (pinfunction "~{4RE}_21") (pintype "input"))
      (node (ref "IC47") (pin "40") (pinfunction "~{1RE}_40") (pintype "input"))
      (node (ref "IC47") (pin "42") (pinfunction "~{2RE}_42") (pintype "input"))
      (node (ref "IC47") (pin "5") (pinfunction "2DE_5") (pintype "input"))
      (node (ref "IC47") (pin "8") (pinfunction "3DE_8") (pintype "input"))
      (node (ref "R219") (pin "1") (pinfunction "1_1") (pintype "passive"))
      (node (ref "SW9") (pin "2") (pinfunction "2_2") (pintype "passive"))
      (node (ref "T28") (pin "1") (pinfunction "G_1") (pintype "passive"))
    )
    (net (code "5") (name "/I2C_SCL") (class "Default")
      (node (ref "B3") (pin "1") (pinfunction "1_1") (pintype "bidirectional"))
      (node (ref "IC42") (pin "14") (pinfunction "SCL_14") (pintype "input"))
      (node (ref "IC52") (pin "1") (pinfunction "SCL_1") (pintype "input"))
      (node (ref "J16") (pin "27") (pinfunction "27_27") (pintype "bidirectional"))
    )
    (net (code "6") (name "/I2C_SDA") (class "Default")
      (node (ref "B2") (pin "1") (pinfunction "1_1") (pintype "bidirectional"))
      (node (ref "IC42") (pin "15") (pinfunction "SDA_15") (pintype "bidirectional"))
      (node (ref "IC52") (pin "3") (pinfunction "SDA_3") (pintype "bidirectional"))
      (node (ref "J16") (pin "26") (pinfunction "26_26") (pintype "bidirectional"))
    )
    (net (code "7") (name "/IO1") (class "Default")
      (node (ref "IC45") (pin "10") (pinfunction "A7_10") (pintype "bidirectional"))
      (node (ref "IC45") (pin "12") (pinfunction "A8_12") (pintype "bidirectional"))
      (node (ref "J14") (pin "1") (pinfunction "1_1") (pintype "bidirectional"))
      (node (ref "R199") (pin "2") (pinfunction "2_2") (pintype "passive"))
      (node (ref "R200") (pin "2") (pinfunction "2_2") (pintype "passive"))
    )
    (net (code "8") (name "/IO2") (class "Default")
      (node (ref "IC45") (pin "7") (pinfunction "A5_7") (pintype "bidirectional"))
      (node (ref "IC45") (pin "9") (pinfunction "A6_9") (pintype "bidirectional"))
      (node (ref "J15") (pin "1") (pinfunction "1_1") (pintype "bidirectional"))
      (node (ref "R202") (pin "2") (pinfunction "2_2") (pintype "passive"))
      (node (ref "R203") (pin "2") (pinfunction "2_2") (pintype "passive"))
    )
    (net (code "9") (name "/IO3") (class "Default")
      (node (ref "IC45") (pin "4") (pinfunction "A3_4") (pintype "bidirectional"))
      (node (ref "IC45") (pin "6") (pinfunction "A4_6") (pintype "bidirectional"))
      (node (ref "J17") (pin "1") (pinfunction "1_1") (pintype "bidirectional"))
      (node (ref "R205") (pin "2") (pinfunction "2_2") (pintype "passive"))
      (node (ref "R206") (pin "2") (pinfunction "2_2") (pintype "passive"))
    )
    (net (code "10") (name "/IO4") (class "Default")
      (node (ref "IC45") (pin "1") (pinfunction "A1_1") (pintype "bidirectional"))
      (node (ref "IC45") (pin "3") (pinfunction "A2_3") (pintype "bidirectional"))
      (node (ref "J18") (pin "1") (pinfunction "1_1") (pintype "bidirectional"))
      (node (ref "R208") (pin "2") (pinfunction "2_2") (pintype "passive"))
      (node (ref "R209") (pin "2") (pinfunction "2_2") (pintype "passive"))
    )
    (net (code "11") (name "/IO5") (class "Default")
      (node (ref "IC51") (pin "10") (pinfunction "A7_10") (pintype "bidirectional"))
      (node (ref "IC51") (pin "12") (pinfunction "A8_12") (pintype "bidirectional"))
      (node (ref "J19") (pin "1") (pinfunction "1_1") (pintype "bidirectional"))
      (node (ref "R222") (pin "2") (pinfunction "2_2") (pintype "passive"))
      (node (ref "R223") (pin "2") (pinfunction "2_2") (pintype "passive"))
    )
    (net (code "12") (name "/IO6") (class "Default")
      (node (ref "IC51") (pin "7") (pinfunction "A5_7") (pintype "bidirectional"))
      (node (ref "IC51") (pin "9") (pinfunction "A6_9") (pintype "bidirectional"))
      (node (ref "J20") (pin "1") (pinfunction "1_1") (pintype "bidirectional"))
      (node (ref "R225") (pin "2") (pinfunction "2_2") (pintype "passive"))
      (node (ref "R226") (pin "2") (pinfunction "2_2") (pintype "passive"))
    )
    (net (code "13") (name "/IO7") (class "Default")
      (node (ref "IC51") (pin "4") (pinfunction "A3_4") (pintype "bidirectional"))
      (node (ref "IC51") (pin "6") (pinfunction "A4_6") (pintype "bidirectional"))
      (node (ref "J21") (pin "1") (pinfunction "1_1") (pintype "bidirectional"))
      (node (ref "R228") (pin "2") (pinfunction "2_2") (pintype "passive"))
      (node (ref "R229") (pin "2") (pinfunction "2_2") (pintype "passive"))
    )
    (net (code "14") (name "/IO8") (class "Default")
      (node (ref "IC51") (pin "1") (pinfunction "A1_1") (pintype "bidirectional"))
      (node (ref "IC51") (pin "3") (pinfunction "A2_3") (pintype "bidirectional"))
      (node (ref "J22") (pin "1") (pinfunction "1_1") (pintype "bidirectional"))
      (node (ref "R232") (pin "2") (pinfunction "2_2") (pintype "passive"))
      (node (ref "R233") (pin "2") (pinfunction "2_2") (pintype "passive"))
    )
    (net (code "15") (name "/LED_OUT1") (class "Default")
      (node (ref "IC43") (pin "6") (pinfunction "A5_6") (pintype "output"))
      (node (ref "IC44") (pin "11") (pinfunction "B5_11") (pintype "input"))
      (node (ref "LD8") (pin "3") (pinfunction "C_3") (pintype "passive"))
      (node (ref "R194") (pin "1") (pinfunction "1_1") (pintype "passive"))
      (node (ref "T27") (pin "1") (pinfunction "G_1") (pintype "passive"))
    )
    (net (code "16") (name "/LED_OUT2") (class "Default")
      (node (ref "IC48") (pin "6") (pinfunction "A5_6") (pintype "output"))
      (node (ref "IC50") (pin "11") (pinfunction "B5_11") (pintype "input"))
      (node (ref "LD11") (pin "3") (pinfunction "C_3") (pintype "passive"))
      (node (ref "R217") (pin "1") (pinfunction "1_1") (pintype "passive"))
      (node (ref "T29") (pin "1") (pinfunction "G_1") (pintype "passive"))
    )
    (net (code "17") (name "/LVDS1_N") (class "Default")
      (node (ref "IC41") (pin "48") (pinfunction "1B_48") (pintype "bidirectional"))
      (node (ref "J16") (pin "3") (pinfunction "3_3") (pintype "bidirectional"))
      (node (ref "R201") (pin "2") (pinfunction "2_2") (pintype "passive"))
    )
    (net (code "18") (name "/LVDS1_P") (class "Default")
      (node (ref "IC41") (pin "47") (pinfunction "1A_47") (pintype "bidirectional"))
      (node (ref "J16") (pin "2") (pinfunction "2_2") (pintype "bidirectional"))
      (node (ref "R201") (pin "1") (pinfunction "1_1") (pintype "passive"))
    )
    (net (code "19") (name "/LVDS2_N") (class "Default")
      (node (ref "IC41") (pin "4") (pinfunction "2B_4") (pintype "bidirectional"))
      (node (ref "J16") (pin "6") (pinfunction "6_6") (pintype "bidirectional"))
      (node (ref "R204") (pin "2") (pinfunction "2_2") (pintype "passive"))
    )
    (net (code "20") (name "/LVDS2_P") (class "Default")
      (node (ref "IC41") (pin "3") (pinfunction "2A_3") (pintype "bidirectional"))
      (node (ref "J16") (pin "5") (pinfunction "5_5") (pintype "bidirectional"))
      (node (ref "R204") (pin "1") (pinfunction "1_1") (pintype "passive"))
    )
    (net (code "21") (name "/LVDS3_N") (class "Default")
      (node (ref "IC41") (pin "10") (pinfunction "3B_10") (pintype "bidirectional"))
      (node (ref "J16") (pin "9") (pinfunction "9_9") (pintype "bidirectional"))
      (node (ref "R207") (pin "2") (pinfunction "2_2") (pintype "passive"))
    )
    (net (code "22") (name "/LVDS3_P") (class "Default")
      (node (ref "IC41") (pin "9") (pinfunction "3A_9") (pintype "bidirectional"))
      (node (ref "J16") (pin "8") (pinfunction "8_8") (pintype "bidirectional"))
      (node (ref "R207") (pin "1") (pinfunction "1_1") (pintype "passive"))
    )
    (net (code "23") (name "/LVDS4_N") (class "Default")
      (node (ref "IC41") (pin "14") (pinfunction "4B_14") (pintype "bidirectional"))
      (node (ref "J16") (pin "12") (pinfunction "12_12") (pintype "bidirectional"))
      (node (ref "R211") (pin "2") (pinfunction "2_2") (pintype "passive"))
    )
    (net (code "24") (name "/LVDS4_P") (class "Default")
      (node (ref "IC41") (pin "13") (pinfunction "4A_13") (pintype "bidirectional"))
      (node (ref "J16") (pin "11") (pinfunction "11_11") (pintype "bidirectional"))
      (node (ref "R211") (pin "1") (pinfunction "1_1") (pintype "passive"))
    )
    (net (code "25") (name "/LVDS5_N") (class "Default")
      (node (ref "IC47") (pin "48") (pinfunction "1B_48") (pintype "bidirectional"))
      (node (ref "J16") (pin "15") (pinfunction "15_15") (pintype "bidirectional"))
      (node (ref "R224") (pin "2") (pinfunction "2_2") (pintype "passive"))
    )
    (net (code "26") (name "/LVDS5_P") (class "Default")
      (node (ref "IC47") (pin "47") (pinfunction "1A_47") (pintype "bidirectional"))
      (node (ref "J16") (pin "14") (pinfunction "14_14") (pintype "bidirectional"))
      (node (ref "R224") (pin "1") (pinfunction "1_1") (pintype "passive"))
    )
    (net (code "27") (name "/LVDS6_N") (class "Default")
      (node (ref "IC47") (pin "4") (pinfunction "2B_4") (pintype "bidirectional"))
      (node (ref "J16") (pin "18") (pinfunction "18_18") (pintype "bidirectional"))
      (node (ref "R227") (pin "2") (pinfunction "2_2") (pintype "passive"))
    )
    (net (code "28") (name "/LVDS6_P") (class "Default")
      (node (ref "IC47") (pin "3") (pinfunction "2A_3") (pintype "bidirectional"))
      (node (ref "J16") (pin "17") (pinfunction "17_17") (pintype "bidirectional"))
      (node (ref "R227") (pin "1") (pinfunction "1_1") (pintype "passive"))
    )
    (net (code "29") (name "/LVDS7_N") (class "Default")
      (node (ref "IC47") (pin "10") (pinfunction "3B_10") (pintype "bidirectional"))
      (node (ref "J16") (pin "21") (pinfunction "21_21") (pintype "bidirectional"))
      (node (ref "R230") (pin "2") (pinfunction "2_2") (pintype "passive"))
    )
    (net (code "30") (name "/LVDS7_P") (class "Default")
      (node (ref "IC47") (pin "9") (pinfunction "3A_9") (pintype "bidirectional"))
      (node (ref "J16") (pin "20") (pinfunction "20_20") (pintype "bidirectional"))
      (node (ref "R230") (pin "1") (pinfunction "1_1") (pintype "passive"))
    )
    (net (code "31") (name "/LVDS8_N") (class "Default")
      (node (ref "IC47") (pin "14") (pinfunction "4B_14") (pintype "bidirectional"))
      (node (ref "J16") (pin "24") (pinfunction "24_24") (pintype "bidirectional"))
      (node (ref "R234") (pin "2") (pinfunction "2_2") (pintype "passive"))
    )
    (net (code "32") (name "/LVDS8_P") (class "Default")
      (node (ref "IC47") (pin "13") (pinfunction "4A_13") (pintype "bidirectional"))
      (node (ref "J16") (pin "23") (pinfunction "23_23") (pintype "bidirectional"))
      (node (ref "R234") (pin "1") (pinfunction "1_1") (pintype "passive"))
    )
    (net (code "33") (name "/TERM_IO1") (class "Default")
      (node (ref "R213") (pin "1") (pinfunction "1_1") (pintype "passive"))
      (node (ref "SW3") (pin "8") (pinfunction "8_8") (pintype "passive"))
      (node (ref "T10") (pin "1") (pinfunction "G_1") (pintype "passive"))
    )
    (net (code "34") (name "/TERM_IO2") (class "Default")
      (node (ref "R214") (pin "1") (pinfunction "1_1") (pintype "passive"))
      (node (ref "SW3") (pin "7") (pinfunction "7_7") (pintype "passive"))
      (node (ref "T11") (pin "1") (pinfunction "G_1") (pintype "passive"))
    )
    (net (code "35") (name "/TERM_IO3") (class "Default")
      (node (ref "R215") (pin "1") (pinfunction "1_1") (pintype "passive"))
      (node (ref "SW3") (pin "6") (pinfunction "6_6") (pintype "passive"))
      (node (ref "T12") (pin "1") (pinfunction "G_1") (pintype "passive"))
    )
    (net (code "36") (name "/TERM_IO4") (class "Default")
      (node (ref "R216") (pin "1") (pinfunction "1_1") (pintype "passive"))
      (node (ref "SW3") (pin "5") (pinfunction "5_5") (pintype "passive"))
      (node (ref "T13") (pin "1") (pinfunction "G_1") (pintype "passive"))
    )
    (net (code "37") (name "/TERM_IO5") (class "Default")
      (node (ref "R238") (pin "1") (pinfunction "1_1") (pintype "passive"))
      (node (ref "SW2") (pin "8") (pinfunction "8_8") (pintype "passive"))
      (node (ref "T14") (pin "1") (pinfunction "G_1") (pintype "passive"))
    )
    (net (code "38") (name "/TERM_IO6") (class "Default")
      (node (ref "R239") (pin "1") (pinfunction "1_1") (pintype "passive"))
      (node (ref "SW2") (pin "7") (pinfunction "7_7") (pintype "passive"))
      (node (ref "T15") (pin "1") (pinfunction "G_1") (pintype "passive"))
    )
    (net (code "39") (name "/TERM_IO7") (class "Default")
      (node (ref "R240") (pin "1") (pinfunction "1_1") (pintype "passive"))
      (node (ref "SW2") (pin "6") (pinfunction "6_6") (pintype "passive"))
      (node (ref "T16") (pin "1") (pinfunction "G_1") (pintype "passive"))
    )
    (net (code "40") (name "/TERM_IO8") (class "Default")
      (node (ref "R241") (pin "1") (pinfunction "1_1") (pintype "passive"))
      (node (ref "SW2") (pin "5") (pinfunction "5_5") (pintype "passive"))
      (node (ref "T17") (pin "1") (pinfunction "G_1") (pintype "passive"))
    )
    (net (code "41") (name "GND") (class "Default")
      (node (ref "B1") (pin "1") (pinfunction "1_1") (pintype "bidirectional"))
      (node (ref "B4") (pin "1") (pinfunction "1_1") (pintype "bidirectional"))
      (node (ref "B6") (pin "1") (pinfunction "1_1") (pintype "bidirectional"))
      (node (ref "C163") (pin "1") (pinfunction "1_1") (pintype "passive"))
      (node (ref "C169") (pin "1") (pinfunction "1_1") (pintype "passive"))
      (node (ref "C170") (pin "2") (pinfunction "2_2") (pintype "passive"))
      (node (ref "C171") (pin "1") (pinfunction "1_1") (pintype "passive"))
      (node (ref "C172") (pin "1") (pinfunction "1_1") (pintype "passive"))
      (node (ref "C173") (pin "1") (pinfunction "1_1") (pintype "passive"))
      (node (ref "C174") (pin "1") (pinfunction "1_1") (pintype "passive"))
      (node (ref "C175") (pin "1") (pinfunction "1_1") (pintype "passive"))
      (node (ref "C176") (pin "1") (pinfunction "1_1") (pintype "passive"))
      (node (ref "C177") (pin "1") (pinfunction "1_1") (pintype "passive"))
      (node (ref "C178") (pin "1") (pinfunction "1_1") (pintype "passive"))
      (node (ref "C179") (pin "2") (pinfunction "2_2") (pintype "passive"))
      (node (ref "C180") (pin "1") (pinfunction "1_1") (pintype "passive"))
      (node (ref "C181") (pin "1") (pinfunction "1_1") (pintype "passive"))
      (node (ref "C182") (pin "1") (pinfunction "1_1") (pintype "passive"))
      (node (ref "C183") (pin "1") (pinfunction "1_1") (pintype "passive"))
      (node (ref "C184") (pin "1") (pinfunction "1_1") (pintype "passive"))
      (node (ref "C185") (pin "1") (pinfunction "1_1") (pintype "passive"))
      (node (ref "C186") (pin "1") (pinfunction "1_1") (pintype "passive"))
      (node (ref "C187") (pin "1") (pinfunction "1_1") (pintype "passive"))
      (node (ref "C188") (pin "2") (pinfunction "2_2") (pintype "passive"))
      (node (ref "C189") (pin "1") (pinfunction "1_1") (pintype "passive"))
      (node (ref "C190") (pin "1") (pinfunction "1_1") (pintype "passive"))
      (node (ref "C191") (pin "1") (pinfunction "1_1") (pintype "passive"))
      (node (ref "C192") (pin "1") (pinfunction "1_1") (pintype "passive"))
      (node (ref "C193") (pin "1") (pinfunction "1_1") (pintype "passive"))
      (node (ref "C194") (pin "2") (pinfunction "2_2") (pintype "passive"))
      (node (ref "C200") (pin "1") (pinfunction "1_1") (pintype "passive"))
      (node (ref "IC1") (pin "1") (pinfunction "-Vin_1") (pintype "power_in"))
      (node (ref "IC2") (pin "1") (pinfunction "-Vin_1") (pintype "power_in"))
      (node (ref "IC41") (pin "18") (pinfunction "GND_18") (pintype "power_in"))
      (node (ref "IC41") (pin "23") (pinfunction "GND_23") (pintype "power_in"))
      (node (ref "IC41") (pin "27") (pinfunction "GND_27") (pintype "power_in"))
      (node (ref "IC41") (pin "31") (pinfunction "GND_31") (pintype "power_in"))
      (node (ref "IC41") (pin "34") (pinfunction "GND_34") (pintype "power_in"))
      (node (ref "IC41") (pin "38") (pinfunction "GND_38") (pintype "power_in"))
      (node (ref "IC41") (pin "43") (pinfunction "GND_43") (pintype "power_in"))
      (node (ref "IC41") (pin "49") (pinfunction "EP_49") (pintype "power_in"))
      (node (ref "IC41") (pin "6") (pinfunction "GND_6") (pintype "power_in"))
      (node (ref "IC41") (pin "7") (pinfunction "GND_7") (pintype "power_in"))
      (node (ref "IC42") (pin "1") (pinfunction "A0_1") (pintype "input"))
      (node (ref "IC42") (pin "8") (pinfunction "GND_8") (pintype "power_in"))
      (node (ref "IC43") (pin "9") (pinfunction "GND2_9") (pintype "power_in"))
      (node (ref "IC44") (pin "8") (pinfunction "GND1_8") (pintype "power_in"))
      (node (ref "IC46") (pin "2") (pinfunction "-Vin_2") (pintype "power_in"))
      (node (ref "IC47") (pin "18") (pinfunction "GND_18") (pintype "power_in"))
      (node (ref "IC47") (pin "23") (pinfunction "GND_23") (pintype "power_in"))
      (node (ref "IC47") (pin "27") (pinfunction "GND_27") (pintype "power_in"))
      (node (ref "IC47") (pin "31") (pinfunction "GND_31") (pintype "power_in"))
      (node (ref "IC47") (pin "34") (pinfunction "GND_34") (pintype "power_in"))
      (node (ref "IC47") (pin "38") (pinfunction "GND_38") (pintype "power_in"))
      (node (ref "IC47") (pin "43") (pinfunction "GND_43") (pintype "power_in"))
      (node (ref "IC47") (pin "49") (pinfunction "EP_49") (pintype "power_in"))
      (node (ref "IC47") (pin "6") (pinfunction "GND_6") (pintype "power_in"))
      (node (ref "IC47") (pin "7") (pinfunction "GND_7") (pintype "power_in"))
      (node (ref "IC48") (pin "9") (pinfunction "GND2_9") (pintype "power_in"))
      (node (ref "IC49") (pin "1") (pinfunction "PGND_1") (pintype "power_in"))
      (node (ref "IC49") (pin "11") (pinfunction "EP_11") (pintype "power_in"))
      (node (ref "IC49") (pin "6") (pinfunction "AGND_6") (pintype "power_in"))
      (node (ref "IC50") (pin "8") (pinfunction "GND1_8") (pintype "power_in"))
      (node (ref "IC52") (pin "2") (pinfunction "VSS_2") (pintype "power_in"))
      (node (ref "IC53") (pin "2") (pinfunction "-Vin_2") (pintype "power_in"))
      (node (ref "J16") (pin "1") (pinfunction "1_1") (pintype "bidirectional"))
      (node (ref "J16") (pin "10") (pinfunction "10_10") (pintype "bidirectional"))
      (node (ref "J16") (pin "13") (pinfunction "13_13") (pintype "bidirectional"))
      (node (ref "J16") (pin "16") (pinfunction "16_16") (pintype "bidirectional"))
      (node (ref "J16") (pin "19") (pinfunction "19_19") (pintype "bidirectional"))
      (node (ref "J16") (pin "22") (pinfunction "22_22") (pintype "bidirectional"))
      (node (ref "J16") (pin "25") (pinfunction "25_25") (pintype "bidirectional"))
      (node (ref "J16") (pin "4") (pinfunction "4_4") (pintype "bidirectional"))
      (node (ref "J16") (pin "7") (pinfunction "7_7") (pintype "bidirectional"))
      (node (ref "LD1") (pin "1") (pinfunction "C_1") (pintype "passive"))
      (node (ref "LD2") (pin "1") (pinfunction "C_1") (pintype "passive"))
      (node (ref "LD3") (pin "1") (pinfunction "C_1") (pintype "passive"))
      (node (ref "R198") (pin "2") (pinfunction "2_2") (pintype "passive"))
      (node (ref "R212") (pin "2") (pinfunction "2_2") (pintype "passive"))
      (node (ref "R221") (pin "2") (pinfunction "2_2") (pintype "passive"))
      (node (ref "R235") (pin "2") (pinfunction "2_2") (pintype "passive"))
      (node (ref "R237") (pin "1") (pinfunction "1_1") (pintype "passive"))
      (node (ref "SW9") (pin "3") (pinfunction "3_3") (pintype "passive"))
      (node (ref "SW9") (pin "4") (pinfunction "4_4") (pintype "passive"))
      (node (ref "T26") (pin "2") (pinfunction "S_2") (pintype "passive"))
      (node (ref "T28") (pin "2") (pinfunction "S_2") (pintype "passive"))
    )
    (net (code "42") (name "GND_ISO1") (class "Default")
      (node (ref "B10") (pin "1") (pinfunction "1_1") (pintype "bidirectional"))
      (node (ref "C164") (pin "1") (pinfunction "1_1") (pintype "passive"))
      (node (ref "C165") (pin "1") (pinfunction "1_1") (pintype "passive"))
      (node (ref "C166") (pin "1") (pinfunction "1_1") (pintype "passive"))
      (node (ref "C167") (pin "1") (pinfunction "1_1") (pintype "passive"))
      (node (ref "C168") (pin "2") (pinfunction "2_2") (pintype "passive"))
      (node (ref "IC1") (pin "7") (pinfunction "-Vout_7") (pintype "power_in"))
      (node (ref "IC43") (pin "8") (pinfunction "GND1_8") (pintype "power_in"))
      (node (ref "IC44") (pin "9") (pinfunction "GND2_9") (pintype "power_in"))
      (node (ref "IC45") (pin "11") (pinfunction "GND_11") (pintype "power_in"))
      (node (ref "IC45") (pin "13") (pinfunction "OE_13") (pintype "input"))
      (node (ref "IC45") (pin "2") (pinfunction "GND_2") (pintype "power_in"))
      (node (ref "IC45") (pin "5") (pinfunction "GND_5") (pintype "power_in"))
      (node (ref "IC45") (pin "8") (pinfunction "GND_8") (pintype "power_in"))
      (node (ref "IC46") (pin "4") (pinfunction "-Vout_4") (pintype "power_in"))
      (node (ref "J14") (pin "2") (pinfunction "2_2") (pintype "bidirectional"))
      (node (ref "J15") (pin "2") (pinfunction "2_2") (pintype "bidirectional"))
      (node (ref "J17") (pin "2") (pinfunction "2_2") (pintype "bidirectional"))
      (node (ref "J18") (pin "2") (pinfunction "2_2") (pintype "bidirectional"))
      (node (ref "LD10") (pin "1") (pinfunction "C_1") (pintype "passive"))
      (node (ref "LD10") (pin "3") (pinfunction "C_3") (pintype "passive"))
      (node (ref "LD8") (pin "1") (pinfunction "C_1") (pintype "passive"))
      (node (ref "LD9") (pin "1") (pinfunction "C_1") (pintype "passive"))
      (node (ref "LD9") (pin "3") (pinfunction "C_3") (pintype "passive"))
      (node (ref "R200") (pin "1") (pinfunction "1_1") (pintype "passive"))
      (node (ref "R203") (pin "1") (pinfunction "1_1") (pintype "passive"))
      (node (ref "R206") (pin "1") (pinfunction "1_1") (pintype "passive"))
      (node (ref "R209") (pin "1") (pinfunction "1_1") (pintype "passive"))
      (node (ref "T10") (pin "2") (pinfunction "S_2") (pintype "passive"))
      (node (ref "T11") (pin "2") (pinfunction "S_2") (pintype "passive"))
      (node (ref "T12") (pin "2") (pinfunction "S_2") (pintype "passive"))
      (node (ref "T13") (pin "2") (pinfunction "S_2") (pintype "passive"))
      (node (ref "T27") (pin "2") (pinfunction "S_2") (pintype "passive"))
    )
    (net (code "43") (name "GND_ISO2") (class "Default")
      (node (ref "B12") (pin "1") (pinfunction "1_1") (pintype "bidirectional"))
      (node (ref "C195") (pin "1") (pinfunction "1_1") (pintype "passive"))
      (node (ref "C196") (pin "1") (pinfunction "1_1") (pintype "passive"))
      (node (ref "C197") (pin "1") (pinfunction "1_1") (pintype "passive"))
      (node (ref "C198") (pin "1") (pinfunction "1_1") (pintype "passive"))
      (node (ref "C199") (pin "2") (pinfunction "2_2") (pintype "passive"))
      (node (ref "IC2") (pin "7") (pinfunction "-Vout_7") (pintype "power_in"))
      (node (ref "IC48") (pin "8") (pinfunction "GND1_8") (pintype "power_in"))
      (node (ref "IC50") (pin "9") (pinfunction "GND2_9") (pintype "power_in"))
      (node (ref "IC51") (pin "11") (pinfunction "GND_11") (pintype "power_in"))
      (node (ref "IC51") (pin "13") (pinfunction "OE_13") (pintype "input"))
      (node (ref "IC51") (pin "2") (pinfunction "GND_2") (pintype "power_in"))
      (node (ref "IC51") (pin "5") (pinfunction "GND_5") (pintype "power_in"))
      (node (ref "IC51") (pin "8") (pinfunction "GND_8") (pintype "power_in"))
      (node (ref "IC53") (pin "4") (pinfunction "-Vout_4") (pintype "power_in"))
      (node (ref "J19") (pin "2") (pinfunction "2_2") (pintype "bidirectional"))
      (node (ref "J20") (pin "2") (pinfunction "2_2") (pintype "bidirectional"))
      (node (ref "J21") (pin "2") (pinfunction "2_2") (pintype "bidirectional"))
      (node (ref "J22") (pin "2") (pinfunction "2_2") (pintype "bidirectional"))
      (node (ref "LD11") (pin "1") (pinfunction "C_1") (pintype "passive"))
      (node (ref "LD12") (pin "1") (pinfunction "C_1") (pintype "passive"))
      (node (ref "LD12") (pin "3") (pinfunction "C_3") (pintype "passive"))
      (node (ref "LD13") (pin "1") (pinfunction "C_1") (pintype "passive"))
      (node (ref "LD13") (pin "3") (pinfunction "C_3") (pintype "passive"))
      (node (ref "R222") (pin "1") (pinfunction "1_1") (pintype "passive"))
      (node (ref "R226") (pin "1") (pinfunction "1_1") (pintype "passive"))
      (node (ref "R229") (pin "1") (pinfunction "1_1") (pintype "passive"))
      (node (ref "R233") (pin "1") (pinfunction "1_1") (pintype "passive"))
      (node (ref "T14") (pin "2") (pinfunction "S_2") (pintype "passive"))
      (node (ref "T15") (pin "2") (pinfunction "S_2") (pintype "passive"))
      (node (ref "T16") (pin "2") (pinfunction "S_2") (pintype "passive"))
      (node (ref "T17") (pin "2") (pinfunction "S_2") (pintype "passive"))
      (node (ref "T29") (pin "2") (pinfunction "S_2") (pintype "passive"))
    )
    (net (code "44") (name "Net-(IC41-1D)") (class "Default")
      (node (ref "IC41") (pin "35") (pinfunction "1D_35") (pintype "input"))
      (node (ref "IC43") (pin "15") (pinfunction "B1_15") (pintype "output"))
    )
    (net (code "45") (name "Net-(IC41-1FSEN)") (class "Default")
      (node (ref "IC41") (pin "20") (pinfunction "3FSEN_20") (pintype "input"))
      (node (ref "IC41") (pin "22") (pinfunction "4FSEN_22") (pintype "input"))
      (node (ref "IC41") (pin "39") (pinfunction "1FSEN_39") (pintype "input"))
      (node (ref "IC41") (pin "41") (pinfunction "2FSEN_41") (pintype "input"))
      (node (ref "R198") (pin "1") (pinfunction "1_1") (pintype "passive"))
      (node (ref "R212") (pin "1") (pinfunction "1_1") (pintype "passive"))
    )
    (net (code "46") (name "Net-(IC41-1R)") (class "Default")
      (node (ref "IC41") (pin "36") (pinfunction "1R_36") (pintype "output"))
      (node (ref "IC44") (pin "2") (pinfunction "A1_2") (pintype "input"))
    )
    (net (code "47") (name "Net-(IC41-2D)") (class "Default")
      (node (ref "IC41") (pin "32") (pinfunction "2D_32") (pintype "input"))
      (node (ref "IC43") (pin "14") (pinfunction "B2_14") (pintype "output"))
    )
    (net (code "48") (name "Net-(IC41-2R)") (class "Default")
      (node (ref "IC41") (pin "33") (pinfunction "2R_33") (pintype "output"))
      (node (ref "IC44") (pin "3") (pinfunction "A2_3") (pintype "input"))
    )
    (net (code "49") (name "Net-(IC41-3D)") (class "Default")
      (node (ref "IC41") (pin "28") (pinfunction "3D_28") (pintype "input"))
      (node (ref "IC43") (pin "13") (pinfunction "B3_13") (pintype "output"))
    )
    (net (code "50") (name "Net-(IC41-3R)") (class "Default")
      (node (ref "IC41") (pin "29") (pinfunction "3R_29") (pintype "output"))
      (node (ref "IC44") (pin "4") (pinfunction "A3_4") (pintype "input"))
    )
    (net (code "51") (name "Net-(IC41-4D)") (class "Default")
      (node (ref "IC41") (pin "25") (pinfunction "4D_25") (pintype "input"))
      (node (ref "IC43") (pin "12") (pinfunction "B4_12") (pintype "output"))
    )
    (net (code "52") (name "Net-(IC41-4R)") (class "Default")
      (node (ref "IC41") (pin "26") (pinfunction "4R_26") (pintype "output"))
      (node (ref "IC44") (pin "5") (pinfunction "A4_5") (pintype "input"))
    )
    (net (code "53") (name "Net-(IC43-A1)") (class "Default")
      (node (ref "IC43") (pin "2") (pinfunction "A1_2") (pintype "input"))
      (node (ref "IC44") (pin "15") (pinfunction "B1_15") (pintype "output"))
      (node (ref "IC45") (pin "14") (pinfunction "B8_14") (pintype "bidirectional"))
      (node (ref "IC45") (pin "15") (pinfunction "B7_15") (pintype "bidirectional"))
    )
    (net (code "54") (name "Net-(IC43-A2)") (class "Default")
      (node (ref "IC43") (pin "3") (pinfunction "A2_3") (pintype "input"))
      (node (ref "IC44") (pin "14") (pinfunction "B2_14") (pintype "output"))
      (node (ref "IC45") (pin "17") (pinfunction "B6_17") (pintype "bidirectional"))
      (node (ref "IC45") (pin "18") (pinfunction "B5_18") (pintype "bidirectional"))
    )
    (net (code "55") (name "Net-(IC43-A3)") (class "Default")
      (node (ref "IC43") (pin "4") (pinfunction "A3_4") (pintype "input"))
      (node (ref "IC44") (pin "13") (pinfunction "B3_13") (pintype "output"))
      (node (ref "IC45") (pin "19") (pinfunction "B4_19") (pintype "bidirectional"))
      (node (ref "IC45") (pin "20") (pinfunction "B3_20") (pintype "bidirectional"))
    )
    (net (code "56") (name "Net-(IC43-A4)") (class "Default")
      (node (ref "IC43") (pin "5") (pinfunction "A4_5") (pintype "input"))
      (node (ref "IC44") (pin "12") (pinfunction "B4_12") (pintype "output"))
      (node (ref "IC45") (pin "22") (pinfunction "B2_22") (pintype "bidirectional"))
      (node (ref "IC45") (pin "23") (pinfunction "B1_23") (pintype "bidirectional"))
    )
    (net (code "57") (name "Net-(IC43-B5)") (class "Default")
      (node (ref "IC43") (pin "11") (pinfunction "B5_11") (pintype "input"))
      (node (ref "R196") (pin "1") (pinfunction "1_1") (pintype "passive"))
      (node (ref "T26") (pin "3") (pinfunction "D_3") (pintype "passive"))
    )
    (net (code "58") (name "Net-(IC45-DIR)") (class "Default")
      (node (ref "IC45") (pin "24") (pinfunction "DIR_24") (pintype "input"))
      (node (ref "R210") (pin "1") (pinfunction "1_1") (pintype "passive"))
      (node (ref "T27") (pin "3") (pinfunction "D_3") (pintype "passive"))
    )
    (net (code "59") (name "Net-(IC47-1D)") (class "Default")
      (node (ref "IC47") (pin "35") (pinfunction "1D_35") (pintype "input"))
      (node (ref "IC48") (pin "15") (pinfunction "B1_15") (pintype "output"))
    )
    (net (code "60") (name "Net-(IC47-1FSEN)") (class "Default")
      (node (ref "IC47") (pin "20") (pinfunction "3FSEN_20") (pintype "input"))
      (node (ref "IC47") (pin "22") (pinfunction "4FSEN_22") (pintype "input"))
      (node (ref "IC47") (pin "39") (pinfunction "1FSEN_39") (pintype "input"))
      (node (ref "IC47") (pin "41") (pinfunction "2FSEN_41") (pintype "input"))
      (node (ref "R221") (pin "1") (pinfunction "1_1") (pintype "passive"))
      (node (ref "R235") (pin "1") (pinfunction "1_1") (pintype "passive"))
    )
    (net (code "61") (name "Net-(IC47-1R)") (class "Default")
      (node (ref "IC47") (pin "36") (pinfunction "1R_36") (pintype "output"))
      (node (ref "IC50") (pin "2") (pinfunction "A1_2") (pintype "input"))
    )
    (net (code "62") (name "Net-(IC47-2D)") (class "Default")
      (node (ref "IC47") (pin "32") (pinfunction "2D_32") (pintype "input"))
      (node (ref "IC48") (pin "14") (pinfunction "B2_14") (pintype "output"))
    )
    (net (code "63") (name "Net-(IC47-2R)") (class "Default")
      (node (ref "IC47") (pin "33") (pinfunction "2R_33") (pintype "output"))
      (node (ref "IC50") (pin "3") (pinfunction "A2_3") (pintype "input"))
    )
    (net (code "64") (name "Net-(IC47-3D)") (class "Default")
      (node (ref "IC47") (pin "28") (pinfunction "3D_28") (pintype "input"))
      (node (ref "IC48") (pin "13") (pinfunction "B3_13") (pintype "output"))
    )
    (net (code "65") (name "Net-(IC47-3R)") (class "Default")
      (node (ref "IC47") (pin "29") (pinfunction "3R_29") (pintype "output"))
      (node (ref "IC50") (pin "4") (pinfunction "A3_4") (pintype "input"))
    )
    (net (code "66") (name "Net-(IC47-4D)") (class "Default")
      (node (ref "IC47") (pin "25") (pinfunction "4D_25") (pintype "input"))
      (node (ref "IC48") (pin "12") (pinfunction "B4_12") (pintype "output"))
    )
    (net (code "67") (name "Net-(IC47-4R)") (class "Default")
      (node (ref "IC47") (pin "26") (pinfunction "4R_26") (pintype "output"))
      (node (ref "IC50") (pin "5") (pinfunction "A4_5") (pintype "input"))
    )
    (net (code "68") (name "Net-(IC48-A1)") (class "Default")
      (node (ref "IC48") (pin "2") (pinfunction "A1_2") (pintype "input"))
      (node (ref "IC50") (pin "15") (pinfunction "B1_15") (pintype "output"))
      (node (ref "IC51") (pin "14") (pinfunction "B8_14") (pintype "bidirectional"))
      (node (ref "IC51") (pin "15") (pinfunction "B7_15") (pintype "bidirectional"))
    )
    (net (code "69") (name "Net-(IC48-A2)") (class "Default")
      (node (ref "IC48") (pin "3") (pinfunction "A2_3") (pintype "input"))
      (node (ref "IC50") (pin "14") (pinfunction "B2_14") (pintype "output"))
      (node (ref "IC51") (pin "17") (pinfunction "B6_17") (pintype "bidirectional"))
      (node (ref "IC51") (pin "18") (pinfunction "B5_18") (pintype "bidirectional"))
    )
    (net (code "70") (name "Net-(IC48-A3)") (class "Default")
      (node (ref "IC48") (pin "4") (pinfunction "A3_4") (pintype "input"))
      (node (ref "IC50") (pin "13") (pinfunction "B3_13") (pintype "output"))
      (node (ref "IC51") (pin "19") (pinfunction "B4_19") (pintype "bidirectional"))
      (node (ref "IC51") (pin "20") (pinfunction "B3_20") (pintype "bidirectional"))
    )
    (net (code "71") (name "Net-(IC48-A4)") (class "Default")
      (node (ref "IC48") (pin "5") (pinfunction "A4_5") (pintype "input"))
      (node (ref "IC50") (pin "12") (pinfunction "B4_12") (pintype "output"))
      (node (ref "IC51") (pin "22") (pinfunction "B2_22") (pintype "bidirectional"))
      (node (ref "IC51") (pin "23") (pinfunction "B1_23") (pintype "bidirectional"))
    )
    (net (code "72") (name "Net-(IC48-B5)") (class "Default")
      (node (ref "IC48") (pin "11") (pinfunction "B5_11") (pintype "input"))
      (node (ref "R218") (pin "1") (pinfunction "1_1") (pintype "passive"))
      (node (ref "T28") (pin "3") (pinfunction "D_3") (pintype "passive"))
    )
    (net (code "73") (name "Net-(IC49-FB)") (class "Default")
      (node (ref "IC49") (pin "5") (pinfunction "FB_5") (pintype "input"))
      (node (ref "R231") (pin "1") (pinfunction "1_1") (pintype "passive"))
      (node (ref "R237") (pin "2") (pinfunction "2_2") (pintype "passive"))
    )
    (net (code "74") (name "Net-(IC49-SW)") (class "Default")
      (node (ref "IC49") (pin "9") (pinfunction "SW_9") (pintype "output"))
      (node (ref "L17") (pin "1") (pinfunction "1_1") (pintype "passive"))
    )
    (net (code "75") (name "Net-(IC51-DIR)") (class "Default")
      (node (ref "IC51") (pin "24") (pinfunction "DIR_24") (pintype "input"))
      (node (ref "R236") (pin "1") (pinfunction "1_1") (pintype "passive"))
      (node (ref "T29") (pin "3") (pinfunction "D_3") (pintype "passive"))
    )
    (net (code "76") (name "Net-(LD1-A)") (class "Default")
      (node (ref "LD1") (pin "2") (pinfunction "A_2") (pintype "passive"))
      (node (ref "R1") (pin "1") (pinfunction "1_1") (pintype "passive"))
    )
    (net (code "77") (name "Net-(LD2-A)") (class "Default")
      (node (ref "LD2") (pin "2") (pinfunction "A_2") (pintype "passive"))
      (node (ref "R2") (pin "2") (pinfunction "2_2") (pintype "passive"))
    )
    (net (code "78") (name "Net-(LD3-A)") (class "Default")
      (node (ref "LD3") (pin "2") (pinfunction "A_2") (pintype "passive"))
      (node (ref "R3") (pin "2") (pinfunction "2_2") (pintype "passive"))
    )
    (net (code "79") (name "Net-(LD8A-A)") (class "Default")
      (node (ref "LD8") (pin "2") (pinfunction "A_2") (pintype "passive"))
      (node (ref "R194") (pin "2") (pinfunction "2_2") (pintype "passive"))
    )
    (net (code "80") (name "Net-(LD8B-A)") (class "Default")
      (node (ref "LD8") (pin "4") (pinfunction "A_4") (pintype "passive"))
      (node (ref "R195") (pin "2") (pinfunction "2_2") (pintype "passive"))
    )
    (net (code "81") (name "Net-(LD9A-A)") (class "Default")
      (node (ref "LD9") (pin "2") (pinfunction "A_2") (pintype "passive"))
      (node (ref "R213") (pin "2") (pinfunction "2_2") (pintype "passive"))
    )
    (net (code "82") (name "Net-(LD9B-A)") (class "Default")
      (node (ref "LD9") (pin "4") (pinfunction "A_4") (pintype "passive"))
      (node (ref "R214") (pin "2") (pinfunction "2_2") (pintype "passive"))
    )
    (net (code "83") (name "Net-(LD10A-A)") (class "Default")
      (node (ref "LD10") (pin "2") (pinfunction "A_2") (pintype "passive"))
      (node (ref "R215") (pin "2") (pinfunction "2_2") (pintype "passive"))
    )
    (net (code "84") (name "Net-(LD10B-A)") (class "Default")
      (node (ref "LD10") (pin "4") (pinfunction "A_4") (pintype "passive"))
      (node (ref "R216") (pin "2") (pinfunction "2_2") (pintype "passive"))
    )
    (net (code "85") (name "Net-(LD11A-A)") (class "Default")
      (node (ref "LD11") (pin "2") (pinfunction "A_2") (pintype "passive"))
      (node (ref "R217") (pin "2") (pinfunction "2_2") (pintype "passive"))
    )
    (net (code "86") (name "Net-(LD11B-A)") (class "Default")
      (node (ref "LD11") (pin "4") (pinfunction "A_4") (pintype "passive"))
      (node (ref "R220") (pin "2") (pinfunction "2_2") (pintype "passive"))
    )
    (net (code "87") (name "Net-(LD12A-A)") (class "Default")
      (node (ref "LD12") (pin "2") (pinfunction "A_2") (pintype "passive"))
      (node (ref "R238") (pin "2") (pinfunction "2_2") (pintype "passive"))
    )
    (net (code "88") (name "Net-(LD12B-A)") (class "Default")
      (node (ref "LD12") (pin "4") (pinfunction "A_4") (pintype "passive"))
      (node (ref "R239") (pin "2") (pinfunction "2_2") (pintype "passive"))
    )
    (net (code "89") (name "Net-(LD13A-A)") (class "Default")
      (node (ref "LD13") (pin "2") (pinfunction "A_2") (pintype "passive"))
      (node (ref "R240") (pin "2") (pinfunction "2_2") (pintype "passive"))
    )
    (net (code "90") (name "Net-(LD13B-A)") (class "Default")
      (node (ref "LD13") (pin "4") (pinfunction "A_4") (pintype "passive"))
      (node (ref "R241") (pin "2") (pinfunction "2_2") (pintype "passive"))
    )
    (net (code "91") (name "Net-(T10-D)") (class "Default")
      (node (ref "R199") (pin "1") (pinfunction "1_1") (pintype "passive"))
      (node (ref "T10") (pin "3") (pinfunction "D_3") (pintype "passive"))
    )
    (net (code "92") (name "Net-(T11-D)") (class "Default")
      (node (ref "R202") (pin "1") (pinfunction "1_1") (pintype "passive"))
      (node (ref "T11") (pin "3") (pinfunction "D_3") (pintype "passive"))
    )
    (net (code "93") (name "Net-(T12-D)") (class "Default")
      (node (ref "R205") (pin "1") (pinfunction "1_1") (pintype "passive"))
      (node (ref "T12") (pin "3") (pinfunction "D_3") (pintype "passive"))
    )
    (net (code "94") (name "Net-(T13-D)") (class "Default")
      (node (ref "R208") (pin "1") (pinfunction "1_1") (pintype "passive"))
      (node (ref "T13") (pin "3") (pinfunction "D_3") (pintype "passive"))
    )
    (net (code "95") (name "Net-(T14-D)") (class "Default")
      (node (ref "R223") (pin "1") (pinfunction "1_1") (pintype "passive"))
      (node (ref "T14") (pin "3") (pinfunction "D_3") (pintype "passive"))
    )
    (net (code "96") (name "Net-(T15-D)") (class "Default")
      (node (ref "R225") (pin "1") (pinfunction "1_1") (pintype "passive"))
      (node (ref "T15") (pin "3") (pinfunction "D_3") (pintype "passive"))
    )
    (net (code "97") (name "Net-(T16-D)") (class "Default")
      (node (ref "R228") (pin "1") (pinfunction "1_1") (pintype "passive"))
      (node (ref "T16") (pin "3") (pinfunction "D_3") (pintype "passive"))
    )
    (net (code "98") (name "Net-(T17-D)") (class "Default")
      (node (ref "R232") (pin "1") (pinfunction "1_1") (pintype "passive"))
      (node (ref "T17") (pin "3") (pinfunction "D_3") (pintype "passive"))
    )
    (net (code "99") (name "P3V3") (class "Default")
      (node (ref "B7") (pin "1") (pinfunction "1_1") (pintype "bidirectional"))
      (node (ref "C171") (pin "2") (pinfunction "2_2") (pintype "passive"))
      (node (ref "C172") (pin "2") (pinfunction "2_2") (pintype "passive"))
      (node (ref "C173") (pin "2") (pinfunction "2_2") (pintype "passive"))
      (node (ref "C174") (pin "2") (pinfunction "2_2") (pintype "passive"))
      (node (ref "C175") (pin "2") (pinfunction "2_2") (pintype "passive"))
      (node (ref "C176") (pin "2") (pinfunction "2_2") (pintype "passive"))
      (node (ref "C177") (pin "2") (pinfunction "2_2") (pintype "passive"))
      (node (ref "C178") (pin "2") (pinfunction "2_2") (pintype "passive"))
      (node (ref "C179") (pin "1") (pinfunction "1_1") (pintype "passive"))
      (node (ref "C180") (pin "2") (pinfunction "2_2") (pintype "passive"))
      (node (ref "C181") (pin "2") (pinfunction "2_2") (pintype "passive"))
      (node (ref "C182") (pin "2") (pinfunction "2_2") (pintype "passive"))
      (node (ref "C183") (pin "2") (pinfunction "2_2") (pintype "passive"))
      (node (ref "C184") (pin "2") (pinfunction "2_2") (pintype "passive"))
      (node (ref "C185") (pin "2") (pinfunction "2_2") (pintype "passive"))
      (node (ref "C186") (pin "2") (pinfunction "2_2") (pintype "passive"))
      (node (ref "C187") (pin "2") (pinfunction "2_2") (pintype "passive"))
      (node (ref "C188") (pin "1") (pinfunction "1_1") (pintype "passive"))
      (node (ref "C189") (pin "2") (pinfunction "2_2") (pintype "passive"))
      (node (ref "C190") (pin "2") (pinfunction "2_2") (pintype "passive"))
      (node (ref "IC41") (pin "11") (pinfunction "VCC_11") (pintype "power_in"))
      (node (ref "IC41") (pin "15") (pinfunction "VCC_15") (pintype "power_in"))
      (node (ref "IC41") (pin "16") (pinfunction "VCC_16") (pintype "power_in"))
      (node (ref "IC41") (pin "2") (pinfunction "VCC_2") (pintype "power_in"))
      (node (ref "IC41") (pin "24") (pinfunction "VCC_24") (pintype "power_in"))
      (node (ref "IC41") (pin "30") (pinfunction "PDN_30") (pintype "input"))
      (node (ref "IC41") (pin "37") (pinfunction "VCC_37") (pintype "power_in"))
      (node (ref "IC41") (pin "45") (pinfunction "VCC_45") (pintype "power_in"))
      (node (ref "IC41") (pin "46") (pinfunction "VCC_46") (pintype "power_in"))
      (node (ref "IC43") (pin "10") (pinfunction "EN2_10") (pintype "input"))
      (node (ref "IC43") (pin "16") (pinfunction "VDD2_16") (pintype "power_in"))
      (node (ref "IC44") (pin "1") (pinfunction "VDD1_1") (pintype "power_in"))
      (node (ref "IC44") (pin "7") (pinfunction "EN1_7") (pintype "input"))
      (node (ref "IC47") (pin "11") (pinfunction "VCC_11") (pintype "power_in"))
      (node (ref "IC47") (pin "15") (pinfunction "VCC_15") (pintype "power_in"))
      (node (ref "IC47") (pin "16") (pinfunction "VCC_16") (pintype "power_in"))
      (node (ref "IC47") (pin "2") (pinfunction "VCC_2") (pintype "power_in"))
      (node (ref "IC47") (pin "24") (pinfunction "VCC_24") (pintype "power_in"))
      (node (ref "IC47") (pin "30") (pinfunction "PDN_30") (pintype "input"))
      (node (ref "IC47") (pin "37") (pinfunction "VCC_37") (pintype "power_in"))
      (node (ref "IC47") (pin "45") (pinfunction "VCC_45") (pintype "power_in"))
      (node (ref "IC47") (pin "46") (pinfunction "VCC_46") (pintype "power_in"))
      (node (ref "IC48") (pin "10") (pinfunction "EN2_10") (pintype "input"))
      (node (ref "IC48") (pin "16") (pinfunction "VDD2_16") (pintype "power_in"))
      (node (ref "IC49") (pin "10") (pinfunction "VOS_10") (pintype "input"))
      (node (ref "IC49") (pin "8") (pinfunction "SLEEP_8") (pintype "input"))
      (node (ref "IC50") (pin "1") (pinfunction "VDD1_1") (pintype "power_in"))
      (node (ref "IC50") (pin "7") (pinfunction "EN1_7") (pintype "input"))
      (node (ref "L17") (pin "2") (pinfunction "2_2") (pintype "passive"))
      (node (ref "R196") (pin "2") (pinfunction "2_2") (pintype "passive"))
      (node (ref "R197") (pin "2") (pinfunction "2_2") (pintype "passive"))
      (node (ref "R2") (pin "1") (pinfunction "1_1") (pintype "passive"))
      (node (ref "R218") (pin "2") (pinfunction "2_2") (pintype "passive"))
      (node (ref "R219") (pin "2") (pinfunction "2_2") (pintype "passive"))
      (node (ref "R231") (pin "2") (pinfunction "2_2") (pintype "passive"))
    )
    (net (code "100") (name "P3V3_MP") (class "Default")
      (node (ref "B5") (pin "1") (pinfunction "1_1") (pintype "bidirectional"))
      (node (ref "C163") (pin "2") (pinfunction "2_2") (pintype "passive"))
      (node (ref "C200") (pin "2") (pinfunction "2_2") (pintype "passive"))
      (node (ref "IC42") (pin "16") (pinfunction "VCC_16") (pintype "bidirectional"))
      (node (ref "IC42") (pin "2") (pinfunction "A1_2") (pintype "input"))
      (node (ref "IC42") (pin "3") (pinfunction "A2_3") (pintype "input"))
      (node (ref "IC52") (pin "4") (pinfunction "VCC_4") (pintype "power_in"))
      (node (ref "J16") (pin "30") (pinfunction "30_30") (pintype "bidirectional"))
      (node (ref "R3") (pin "1") (pinfunction "1_1") (pintype "passive"))
    )
    (net (code "101") (name "P5V0_ISO1") (class "Default")
      (node (ref "B9") (pin "1") (pinfunction "1_1") (pintype "bidirectional"))
      (node (ref "C164") (pin "2") (pinfunction "2_2") (pintype "passive"))
      (node (ref "C165") (pin "2") (pinfunction "2_2") (pintype "passive"))
      (node (ref "C166") (pin "2") (pinfunction "2_2") (pintype "passive"))
      (node (ref "C167") (pin "2") (pinfunction "2_2") (pintype "passive"))
      (node (ref "C168") (pin "1") (pinfunction "1_1") (pintype "passive"))
      (node (ref "IC1") (pin "8") (pinfunction "+Vout_8") (pintype "power_in"))
      (node (ref "IC43") (pin "1") (pinfunction "VDD1_1") (pintype "power_in"))
      (node (ref "IC43") (pin "7") (pinfunction "EN1_7") (pintype "input"))
      (node (ref "IC44") (pin "10") (pinfunction "EN2_10") (pintype "input"))
      (node (ref "IC44") (pin "16") (pinfunction "VDD2_16") (pintype "power_in"))
      (node (ref "IC45") (pin "16") (pinfunction "VCC_16") (pintype "power_in"))
      (node (ref "IC45") (pin "21") (pinfunction "VCC_21") (pintype "power_in"))
      (node (ref "IC46") (pin "6") (pinfunction "+Vout_6") (pintype "power_in"))
      (node (ref "R195") (pin "1") (pinfunction "1_1") (pintype "passive"))
      (node (ref "R210") (pin "2") (pinfunction "2_2") (pintype "passive"))
      (node (ref "SW3") (pin "1") (pinfunction "1_1") (pintype "passive"))
      (node (ref "SW3") (pin "2") (pinfunction "2_2") (pintype "passive"))
      (node (ref "SW3") (pin "3") (pinfunction "3_3") (pintype "passive"))
      (node (ref "SW3") (pin "4") (pinfunction "4_4") (pintype "passive"))
    )
    (net (code "102") (name "P5V0_ISO2") (class "Default")
      (node (ref "B11") (pin "1") (pinfunction "1_1") (pintype "bidirectional"))
      (node (ref "C195") (pin "2") (pinfunction "2_2") (pintype "passive"))
      (node (ref "C196") (pin "2") (pinfunction "2_2") (pintype "passive"))
      (node (ref "C197") (pin "2") (pinfunction "2_2") (pintype "passive"))
      (node (ref "C198") (pin "2") (pinfunction "2_2") (pintype "passive"))
      (node (ref "C199") (pin "1") (pinfunction "1_1") (pintype "passive"))
      (node (ref "IC2") (pin "8") (pinfunction "+Vout_8") (pintype "power_in"))
      (node (ref "IC48") (pin "1") (pinfunction "VDD1_1") (pintype "power_in"))
      (node (ref "IC48") (pin "7") (pinfunction "EN1_7") (pintype "input"))
      (node (ref "IC50") (pin "10") (pinfunction "EN2_10") (pintype "input"))
      (node (ref "IC50") (pin "16") (pinfunction "VDD2_16") (pintype "power_in"))
      (node (ref "IC51") (pin "16") (pinfunction "VCC_16") (pintype "power_in"))
      (node (ref "IC51") (pin "21") (pinfunction "VCC_21") (pintype "power_in"))
      (node (ref "IC53") (pin "6") (pinfunction "+Vout_6") (pintype "power_in"))
      (node (ref "R220") (pin "1") (pinfunction "1_1") (pintype "passive"))
      (node (ref "R236") (pin "2") (pinfunction "2_2") (pintype "passive"))
      (node (ref "SW2") (pin "1") (pinfunction "1_1") (pintype "passive"))
      (node (ref "SW2") (pin "2") (pinfunction "2_2") (pintype "passive"))
      (node (ref "SW2") (pin "3") (pinfunction "3_3") (pintype "passive"))
      (node (ref "SW2") (pin "4") (pinfunction "4_4") (pintype "passive"))
    )
    (net (code "103") (name "P12V0") (class "Default")
      (node (ref "B8") (pin "1") (pinfunction "1_1") (pintype "bidirectional"))
      (node (ref "C169") (pin "2") (pinfunction "2_2") (pintype "passive"))
      (node (ref "C170") (pin "1") (pinfunction "1_1") (pintype "passive"))
      (node (ref "C191") (pin "2") (pinfunction "2_2") (pintype "passive"))
      (node (ref "C192") (pin "2") (pinfunction "2_2") (pintype "passive"))
      (node (ref "C193") (pin "2") (pinfunction "2_2") (pintype "passive"))
      (node (ref "C194") (pin "1") (pinfunction "1_1") (pintype "passive"))
      (node (ref "IC1") (pin "3") (pinfunction "+Vin_3") (pintype "power_in"))
      (node (ref "IC2") (pin "3") (pinfunction "+Vin_3") (pintype "power_in"))
      (node (ref "IC46") (pin "1") (pinfunction "+Vin_1") (pintype "power_in"))
      (node (ref "IC49") (pin "2") (pinfunction "VIN_2") (pintype "input"))
      (node (ref "IC49") (pin "3") (pinfunction "EN_3") (pintype "input"))
      (node (ref "IC53") (pin "1") (pinfunction "+Vin_1") (pintype "power_in"))
      (node (ref "J16") (pin "28") (pinfunction "28_28") (pintype "bidirectional"))
      (node (ref "J16") (pin "29") (pinfunction "29_29") (pintype "bidirectional"))
      (node (ref "R1") (pin "2") (pinfunction "2_2") (pintype "passive"))
    )
    (net (code "104") (name "unconnected-(IC1-na-Pad14)") (class "Default")
      (node (ref "IC1") (pin "14") (pinfunction "na_14") (pintype "passive"))
    )
    (net (code "105") (name "unconnected-(IC2-na-Pad14)") (class "Default")
      (node (ref "IC2") (pin "14") (pinfunction "na_14") (pintype "passive"))
    )
    (net (code "106") (name "unconnected-(IC41-NC-Pad17)") (class "Default")
      (node (ref "IC41") (pin "17") (pinfunction "NC_17") (pintype "passive"))
    )
    (net (code "107") (name "unconnected-(IC41-NC-Pad44)") (class "Default")
      (node (ref "IC41") (pin "44") (pinfunction "NC_44") (pintype "passive"))
    )
    (net (code "108") (name "unconnected-(IC42-~{INT}-Pad13)") (class "Default")
      (node (ref "IC42") (pin "13") (pinfunction "~{INT}_13") (pintype "output"))
    )
    (net (code "109") (name "unconnected-(IC47-NC-Pad17)") (class "Default")
      (node (ref "IC47") (pin "17") (pinfunction "NC_17") (pintype "passive"))
    )
    (net (code "110") (name "unconnected-(IC47-NC-Pad44)") (class "Default")
      (node (ref "IC47") (pin "44") (pinfunction "NC_44") (pintype "passive"))
    )
    (net (code "111") (name "unconnected-(IC49-NC-Pad4)") (class "Default")
      (node (ref "IC49") (pin "4") (pinfunction "NC_4") (pintype "passive"))
    )
    (net (code "112") (name "unconnected-(IC49-PG-Pad7)") (class "Default")
      (node (ref "IC49") (pin "7") (pinfunction "PG_7") (pintype "output"))
    )
    (net (code "113") (name "unconnected-(IC52-NC-Pad5)") (class "Default")
      (node (ref "IC52") (pin "5") (pinfunction "NC_5") (pintype "passive"))
    )
  )
)
